# Main_board_V5_0.net
KiCad netlist of a schematic drawn in EAGLE
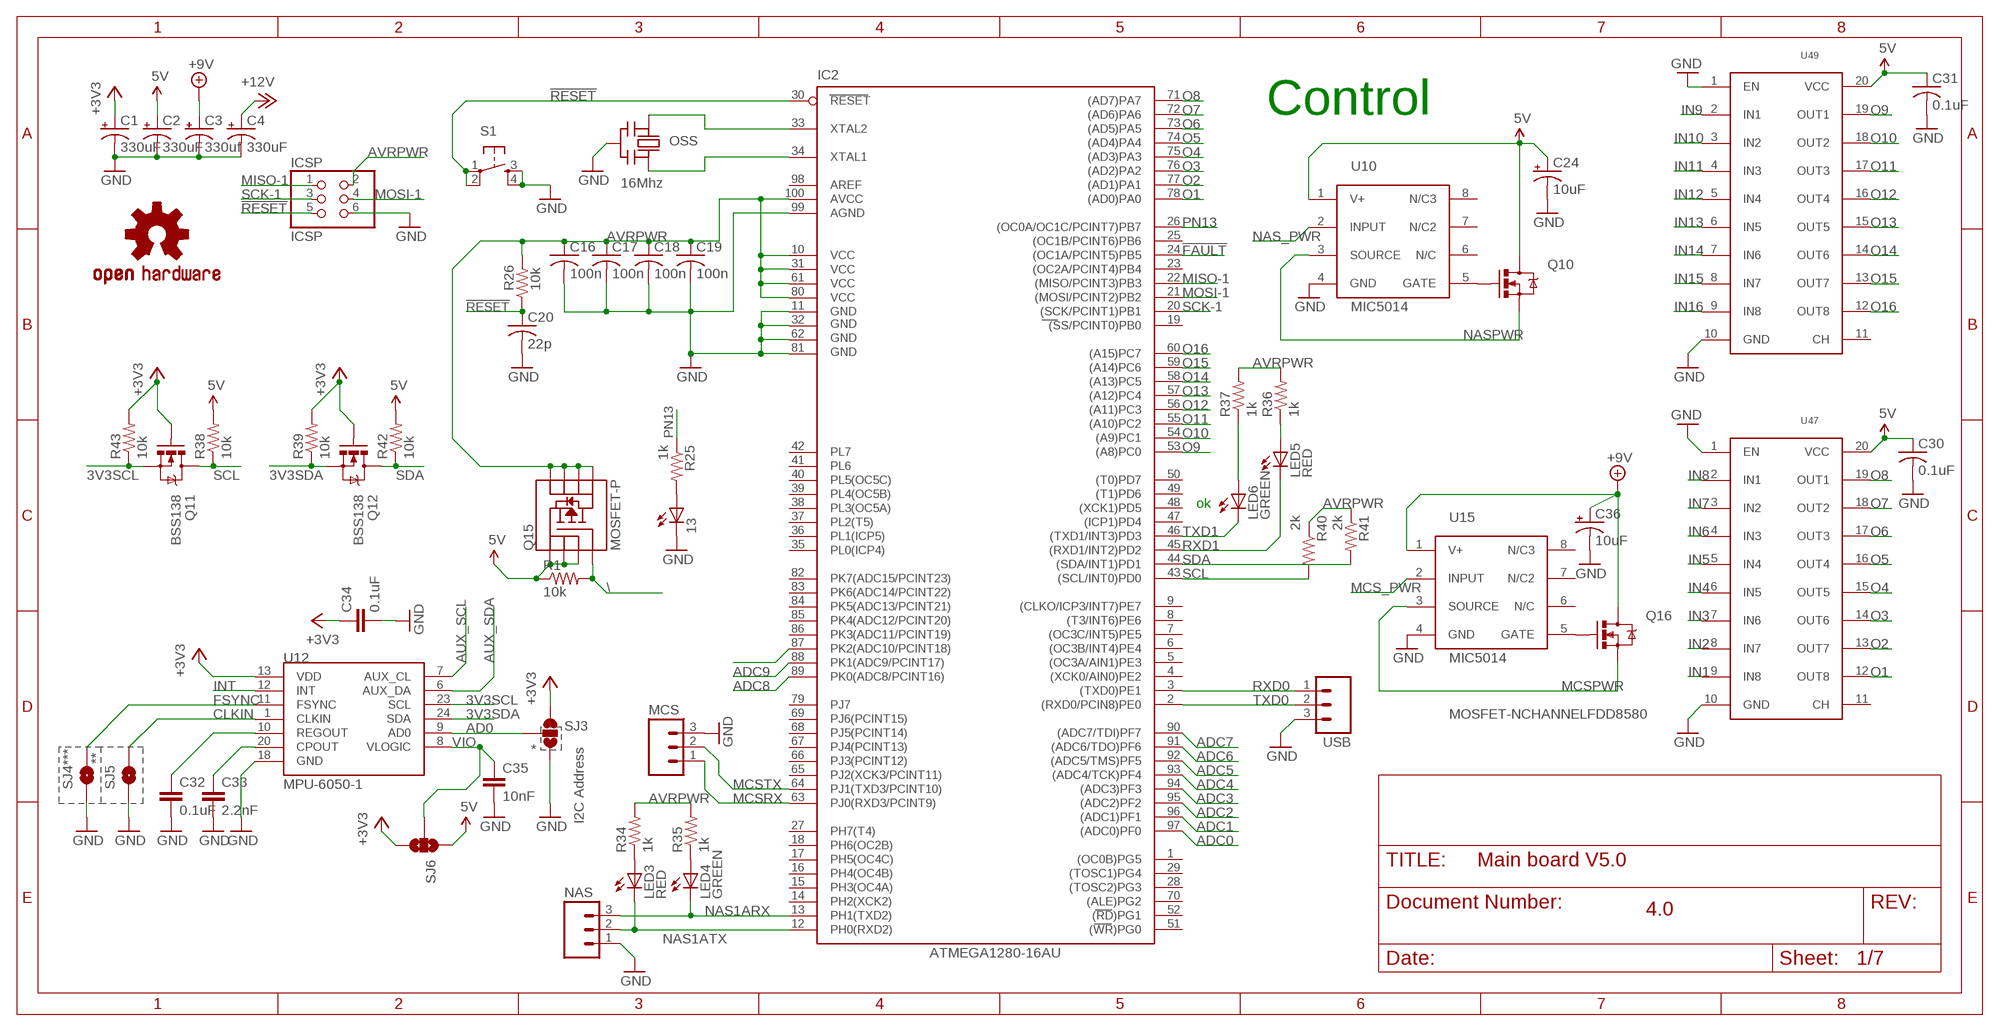
[diagram p0: schematic, sheet 1]
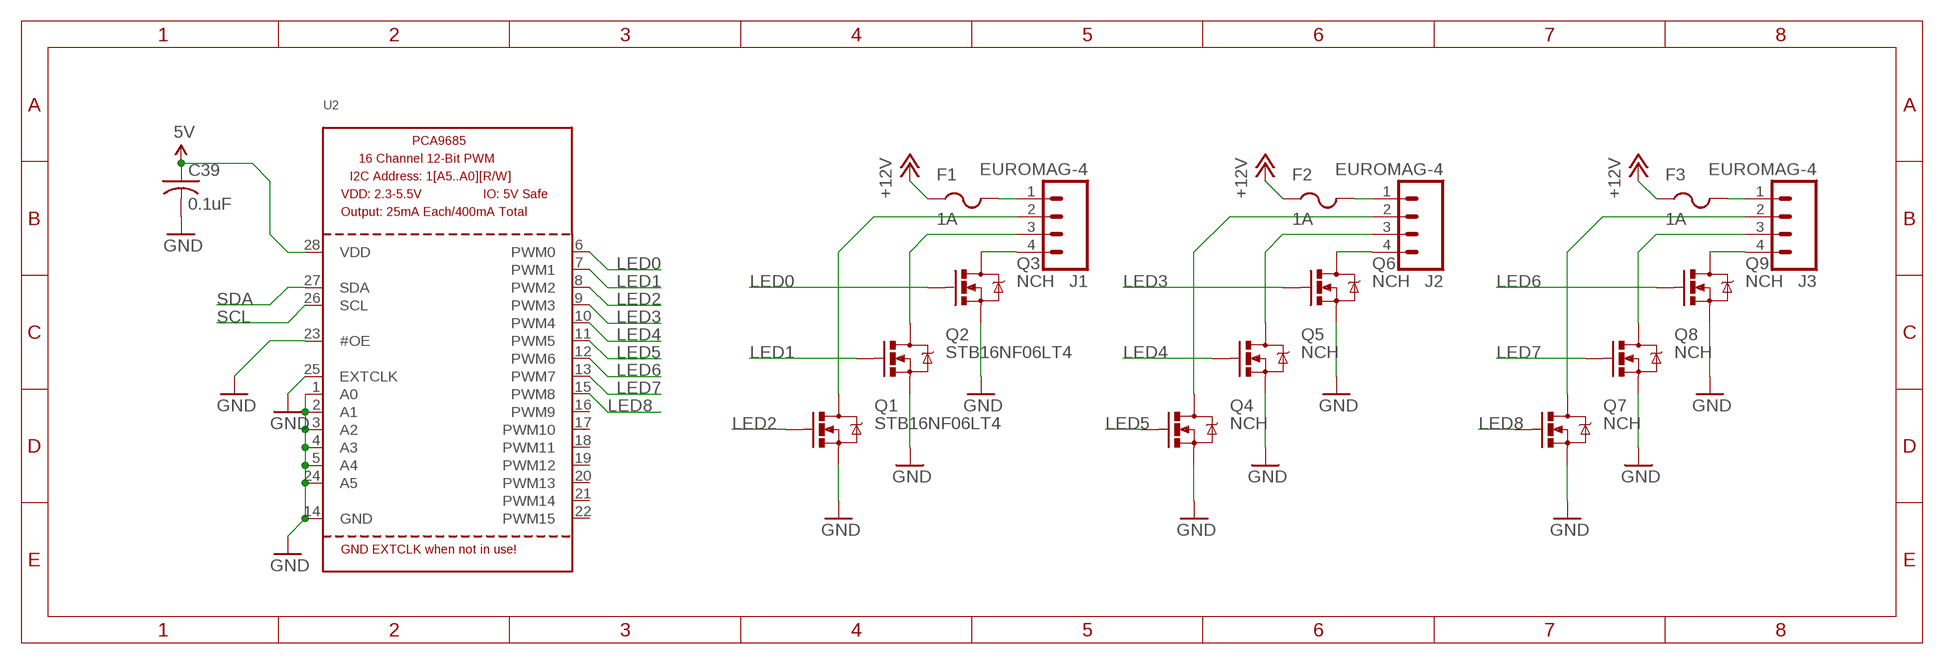
[diagram p1: schematic, sheet 2]
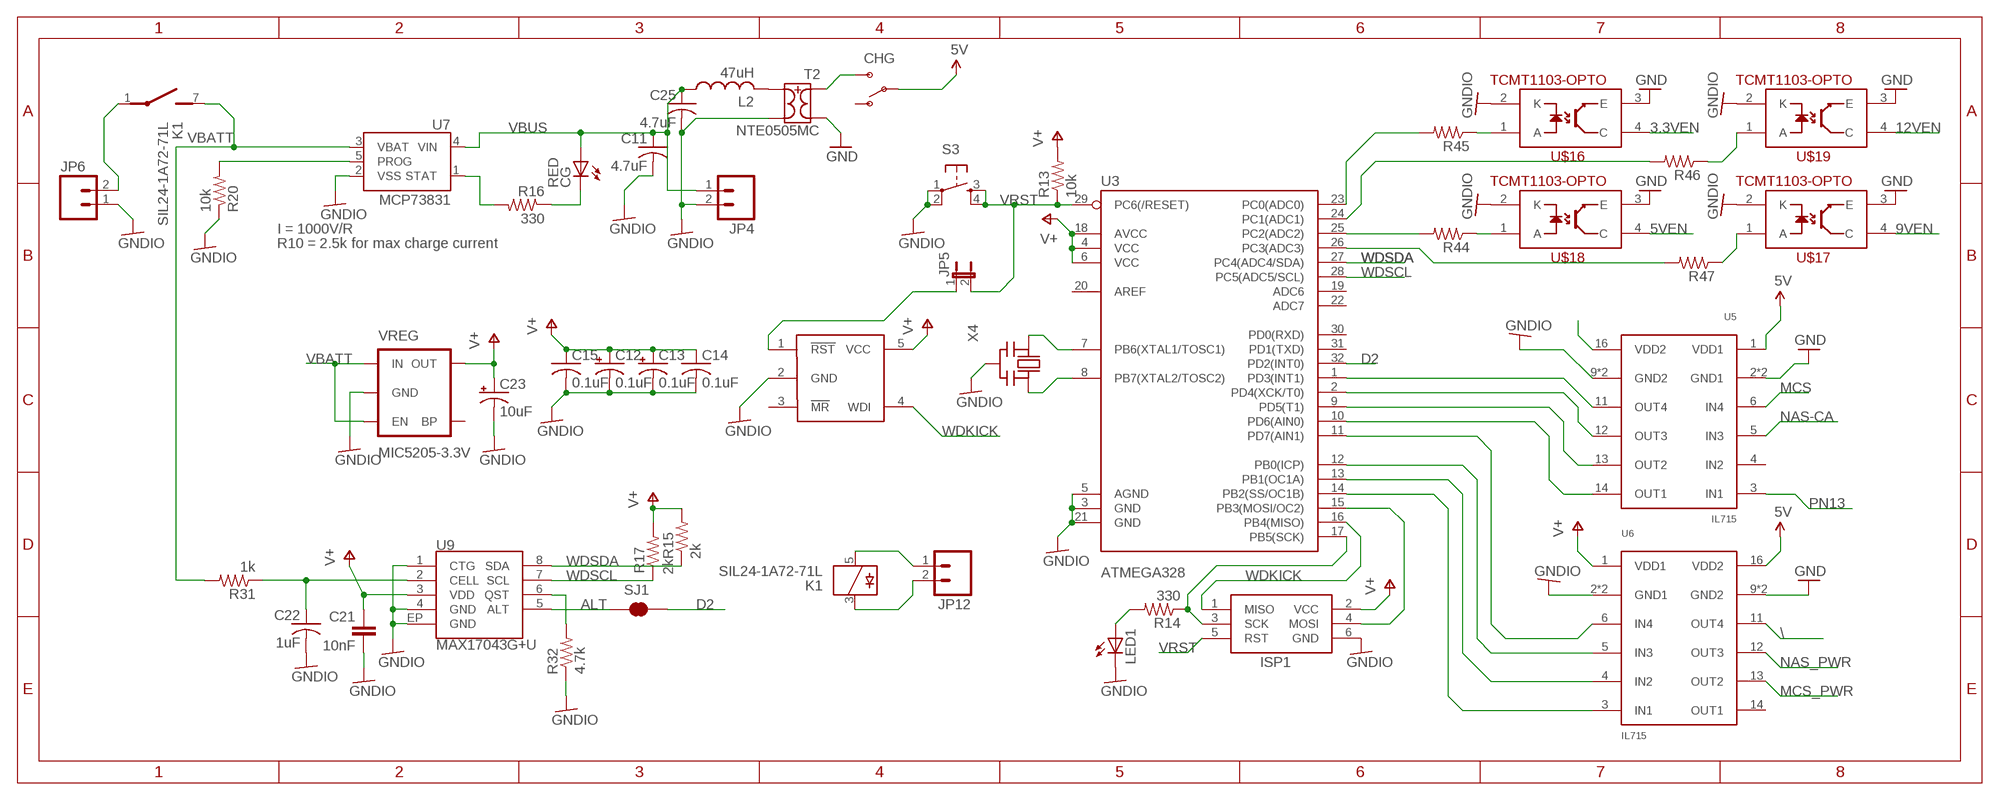
[diagram p2: schematic, sheet 3]
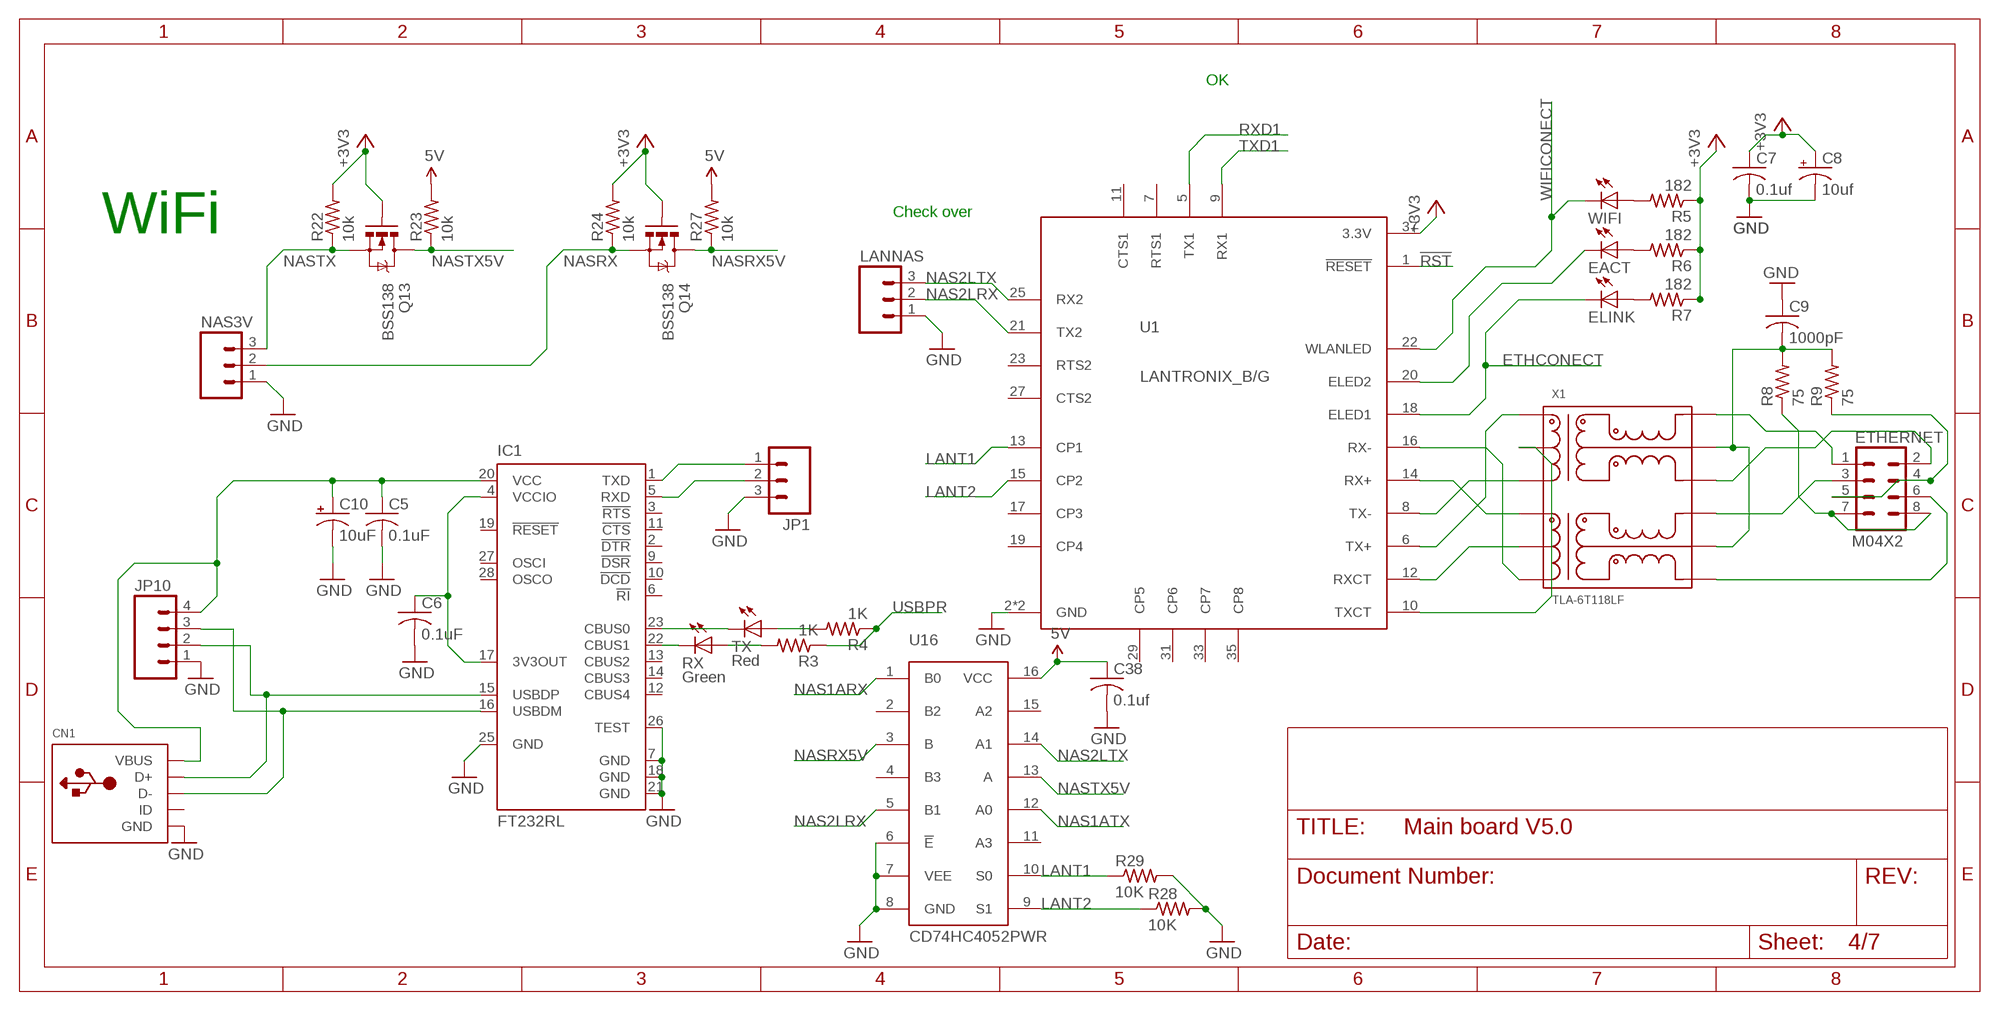
[diagram p3: schematic, sheet 4]
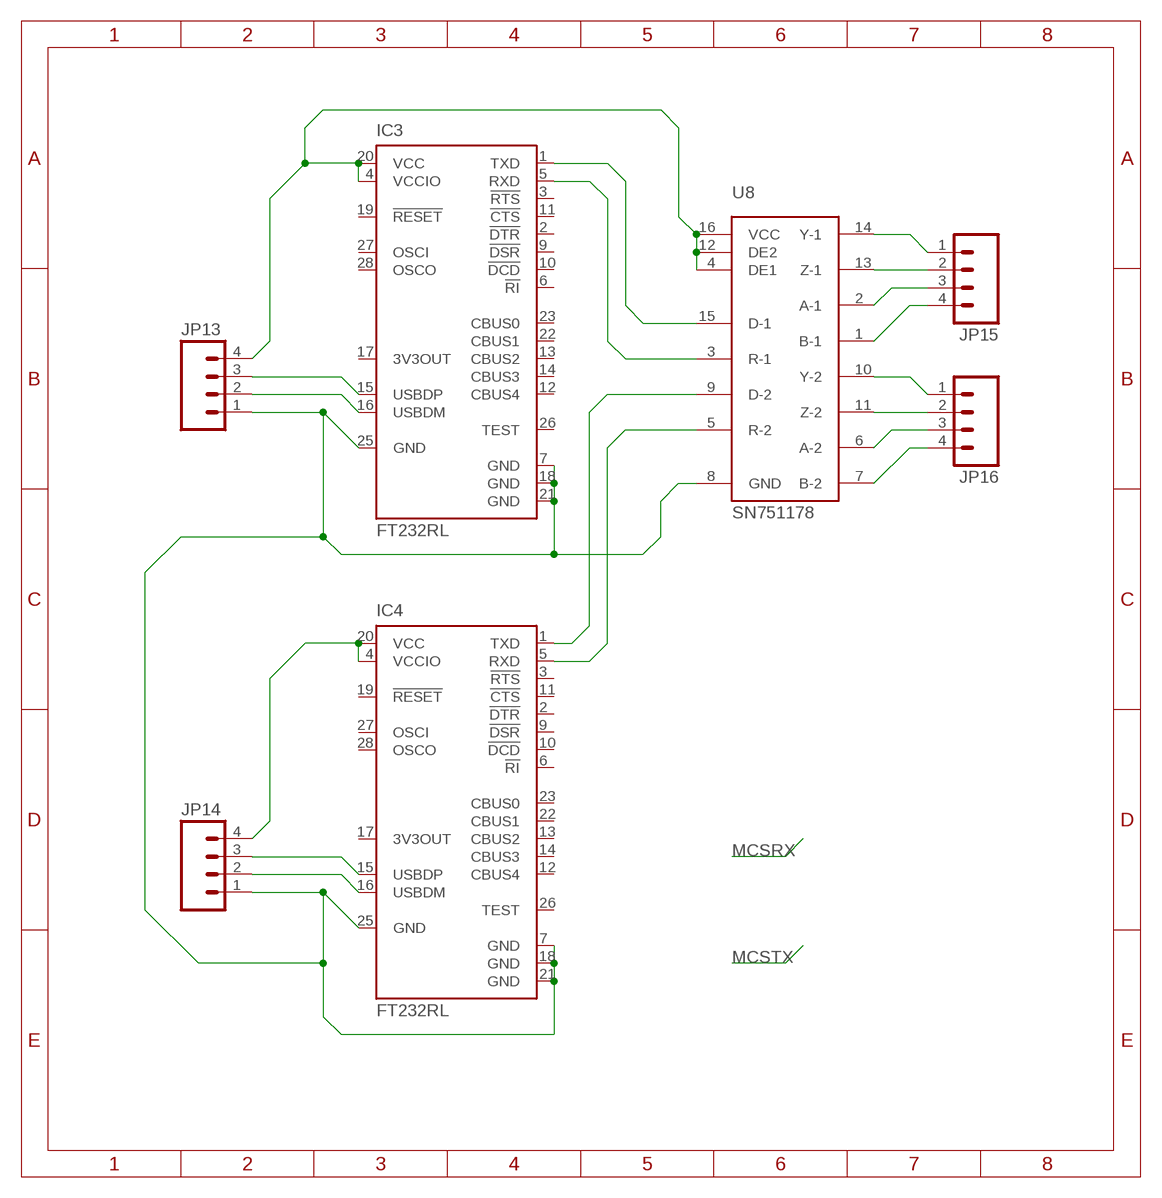
[diagram p4: schematic, sheet 5]
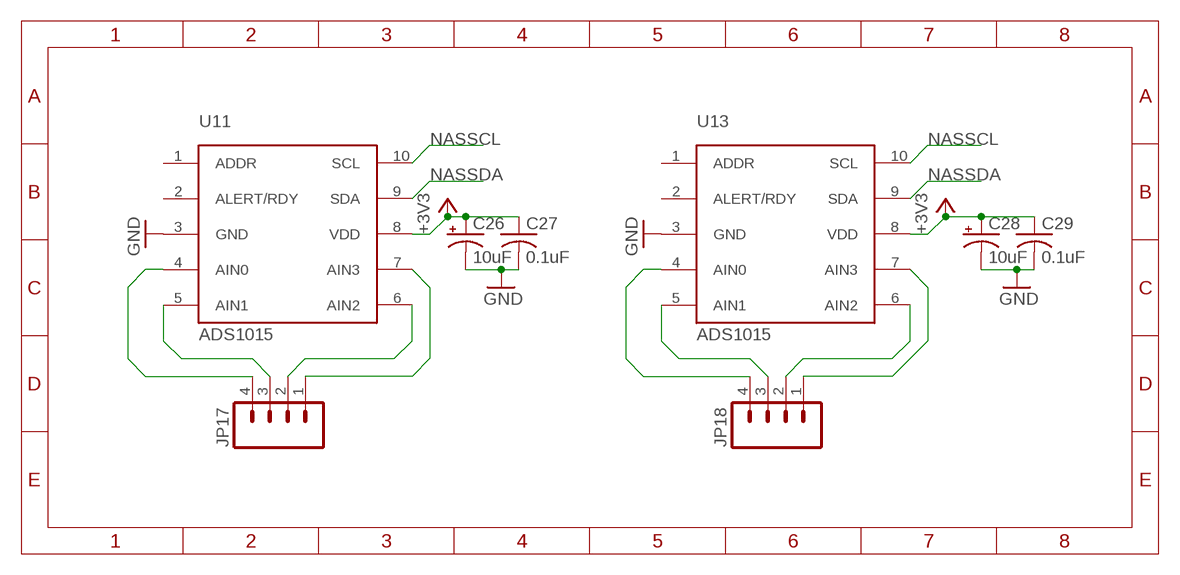
[diagram p5: schematic, sheet 6]
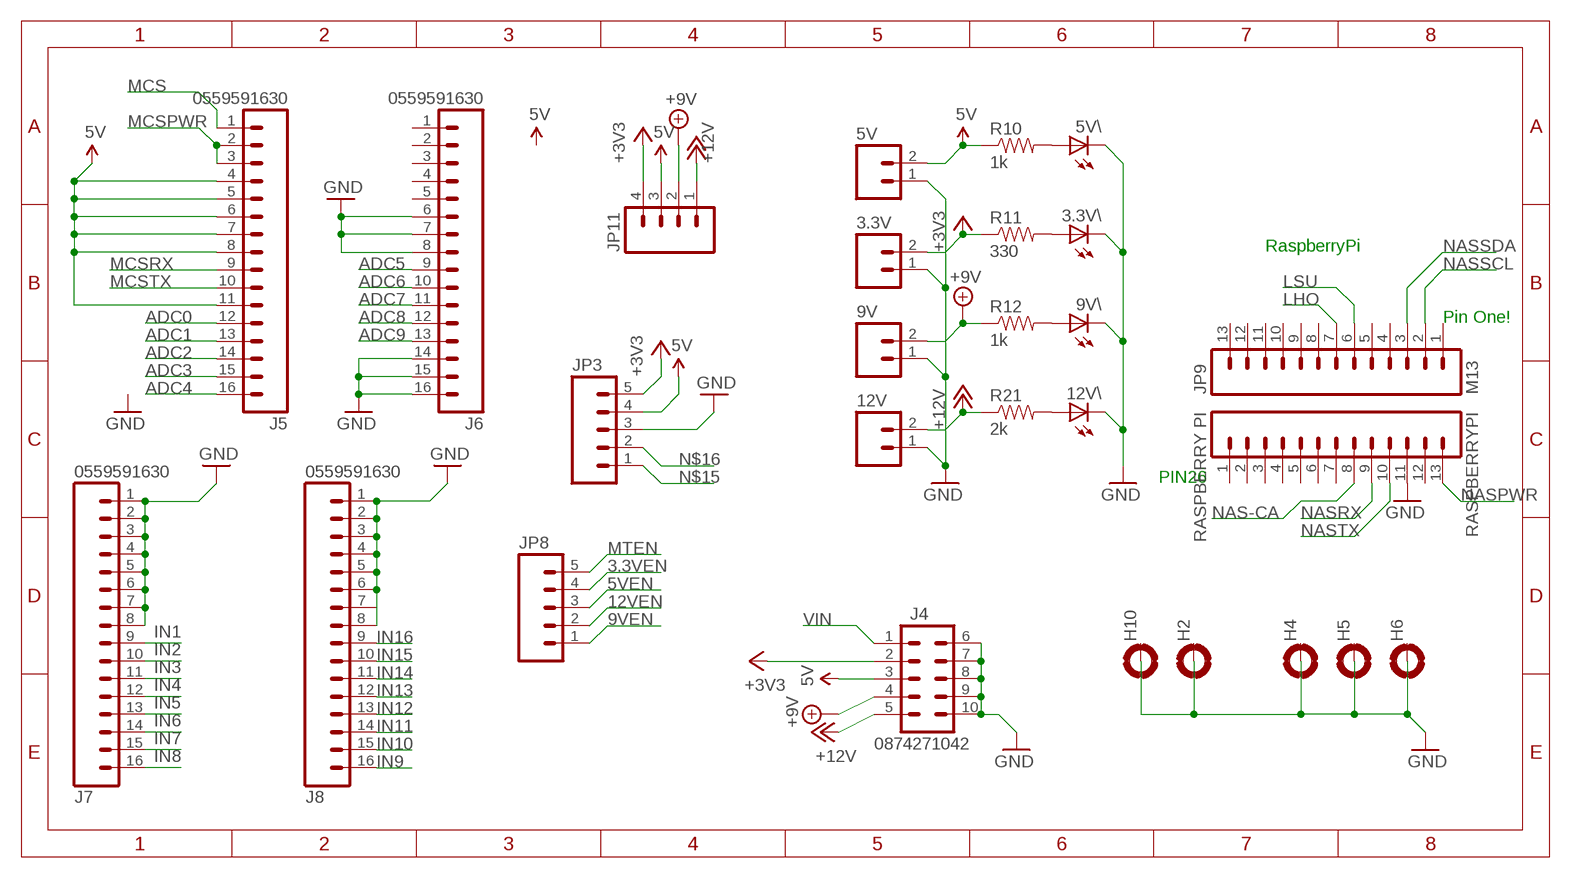
[diagram p6: schematic, sheet 7]

(export (version "E")
  (design (tool "Eeschema 10.0.6"))
  (components
    (comp (ref "C5")
      (value "0.1uF")
      (footprint "eagle-import:C0805K")
      (libsource (lib "eagle-import") (part "C-USC0805K"))
    )
    (comp (ref "C6")
      (value "0.1uF")
      (footprint "eagle-import:C0805K")
      (libsource (lib "eagle-import") (part "C-USC0805K"))
    )
    (comp (ref "C7")
      (value "0.1uf")
      (footprint "eagle-import:C0805K")
      (libsource (lib "eagle-import") (part "C-USC0805K"))
    )
    (comp (ref "C8")
      (value "10uf")
      (footprint "eagle-import:EIA3528")
      (libsource (lib "eagle-import") (part "CAP_POL3528"))
    )
    (comp (ref "C9")
      (value "1000pF")
      (footprint "eagle-import:C1812")
      (libsource (lib "eagle-import") (part "C-USC1812"))
    )
    (comp (ref "C10")
      (value "10uF")
      (footprint "eagle-import:EIA3528-KIT")
      (libsource (lib "eagle-import") (part "CAP_POL3528-KIT"))
    )
    (comp (ref "C38")
      (value "0.1uf")
      (footprint "eagle-import:C0805K")
      (libsource (lib "eagle-import") (part "C-USC0805K"))
    )
    (comp (ref "CN1")
      (value "USBMINIB")
      (footprint "eagle-import:USB-MINIB")
      (libsource (lib "eagle-import") (part "USBMINIB"))
    )
    (comp (ref "EACT")
      (value "LEDCHIP-LED0805")
      (footprint "eagle-import:CHIP-LED0805")
      (libsource (lib "eagle-import") (part "LEDCHIP-LED0805"))
    )
    (comp (ref "ELINK")
      (value "LEDCHIP-LED0805")
      (footprint "eagle-import:CHIP-LED0805")
      (libsource (lib "eagle-import") (part "LEDCHIP-LED0805"))
    )
    (comp (ref "ETHERNET")
      (value "M04X2")
      (footprint "eagle-import:2X4")
      (libsource (lib "eagle-import") (part "M04X2"))
    )
    (comp (ref "IC1")
      (value "FT232RL")
      (footprint "eagle-import:SSOP28")
      (libsource (lib "eagle-import") (part "FT232RL"))
    )
    (comp (ref "JP1")
      (value "M03POLAR")
      (footprint "eagle-import:MOLEX-1X3")
      (libsource (lib "eagle-import") (part "M03POLAR"))
    )
    (comp (ref "JP10")
      (value "M04POLAR")
      (footprint "eagle-import:MOLEX-1X4")
      (libsource (lib "eagle-import") (part "M04POLAR"))
    )
    (comp (ref "LANNAS")
      (value "M03POLAR")
      (footprint "eagle-import:MOLEX-1X3")
      (libsource (lib "eagle-import") (part "M03POLAR"))
    )
    (comp (ref "NAS3V")
      (value "M03LOCK_NO_SILK")
      (footprint "eagle-import:1X03_LOCK_NO_SILK")
      (libsource (lib "eagle-import") (part "M03LOCK_NO_SILK"))
    )
    (comp (ref "Q13")
      (value "BSS138")
      (footprint "eagle-import:SOT23-3")
      (libsource (lib "eagle-import") (part "MOSFET-NCHANNELSMD"))
    )
    (comp (ref "Q14")
      (value "BSS138")
      (footprint "eagle-import:SOT23-3")
      (libsource (lib "eagle-import") (part "MOSFET-NCHANNELSMD"))
    )
    (comp (ref "R3")
      (value "1K")
      (footprint "eagle-import:R0805")
      (libsource (lib "eagle-import") (part "R-US_R0805"))
    )
    (comp (ref "R4")
      (value "1K")
      (footprint "eagle-import:R0805")
      (libsource (lib "eagle-import") (part "R-US_R0805"))
    )
    (comp (ref "R5")
      (value "182")
      (footprint "eagle-import:R0805")
      (libsource (lib "eagle-import") (part "R-US_R0805"))
    )
    (comp (ref "R6")
      (value "182")
      (footprint "eagle-import:R0805")
      (libsource (lib "eagle-import") (part "R-US_R0805"))
    )
    (comp (ref "R7")
      (value "182")
      (footprint "eagle-import:R0805")
      (libsource (lib "eagle-import") (part "R-US_R0805"))
    )
    (comp (ref "R8")
      (value "75")
      (footprint "eagle-import:R0805")
      (libsource (lib "eagle-import") (part "R-US_R0805"))
    )
    (comp (ref "R9")
      (value "75")
      (footprint "eagle-import:R0805")
      (libsource (lib "eagle-import") (part "R-US_R0805"))
    )
    (comp (ref "R22")
      (value "10k")
      (footprint "eagle-import:R0805")
      (libsource (lib "eagle-import") (part "R-US_R0805"))
    )
    (comp (ref "R23")
      (value "10k")
      (footprint "eagle-import:R0805")
      (libsource (lib "eagle-import") (part "R-US_R0805"))
    )
    (comp (ref "R24")
      (value "10k")
      (footprint "eagle-import:R0805")
      (libsource (lib "eagle-import") (part "R-US_R0805"))
    )
    (comp (ref "R27")
      (value "10k")
      (footprint "eagle-import:R0805")
      (libsource (lib "eagle-import") (part "R-US_R0805"))
    )
    (comp (ref "R28")
      (value "10K")
      (footprint "eagle-import:R0805")
      (libsource (lib "eagle-import") (part "R-US_R0805"))
    )
    (comp (ref "R29")
      (value "10K")
      (footprint "eagle-import:R0805")
      (libsource (lib "eagle-import") (part "R-US_R0805"))
    )
    (comp (ref "RX")
      (value "Green")
      (footprint "eagle-import:CHIP-LED0805")
      (libsource (lib "eagle-import") (part "LEDCHIP-LED0805"))
    )
    (comp (ref "TX")
      (value "Red")
      (footprint "eagle-import:CHIP-LED0805")
      (libsource (lib "eagle-import") (part "LEDCHIP-LED0805"))
    )
    (comp (ref "U1")
      (value "LANTRONIX_B/G")
      (footprint "eagle-import:LANA_BTH")
      (libsource (lib "eagle-import") (part "LANTRONIX_A/B"))
    )
    (comp (ref "U16")
      (value "CD74HC4052PWR")
      (footprint "eagle-import:TSSOP-16")
      (libsource (lib "eagle-import") (part "CD74HC4052PWR"))
    )
    (comp (ref "WIFI")
      (value "LEDCHIP-LED0805")
      (footprint "eagle-import:CHIP-LED0805")
      (libsource (lib "eagle-import") (part "LEDCHIP-LED0805"))
    )
    (comp (ref "X1")
      (value "TLA-6T118LF")
      (footprint "eagle-import:SO-16MOD")
      (libsource (lib "eagle-import") (part "TLA-6T118LF"))
    )
    (comp (ref "C39")
      (value "0.1uF")
      (footprint "eagle-import:C0603")
      (libsource (lib "eagle-import") (part "minimidi_C-USC0603"))
    )
    (comp (ref "F1")
      (value "1A")
      (footprint "eagle-import:1812")
      (libsource (lib "eagle-import") (part "PTCFUSE-1812"))
    )
    (comp (ref "F2")
      (value "1A")
      (footprint "eagle-import:1812")
      (libsource (lib "eagle-import") (part "PTCFUSE-1812"))
    )
    (comp (ref "F3")
      (value "1A")
      (footprint "eagle-import:1812")
      (libsource (lib "eagle-import") (part "PTCFUSE-1812"))
    )
    (comp (ref "J1")
      (value "EUROMAG-4")
      (footprint "eagle-import:M4")
      (libsource (lib "eagle-import") (part "EUROMAG-4"))
    )
    (comp (ref "J2")
      (value "EUROMAG-4")
      (footprint "eagle-import:M4")
      (libsource (lib "eagle-import") (part "EUROMAG-4"))
    )
    (comp (ref "J3")
      (value "EUROMAG-4")
      (footprint "eagle-import:M4")
      (libsource (lib "eagle-import") (part "EUROMAG-4"))
    )
    (comp (ref "Q1")
      (value "STB16NF06LT4")
      (footprint "eagle-import:DPAK")
      (libsource (lib "eagle-import") (part "MOSFET-NCHANNELFDD8580"))
    )
    (comp (ref "Q2")
      (value "STB16NF06LT4")
      (footprint "eagle-import:DPAK")
      (libsource (lib "eagle-import") (part "MOSFET-NCHANNELFDD8580"))
    )
    (comp (ref "Q3")
      (value "NCH")
      (footprint "eagle-import:DPAK")
      (libsource (lib "eagle-import") (part "MOSFET-NCHANNELFDD8580"))
    )
    (comp (ref "Q4")
      (value "NCH")
      (footprint "eagle-import:DPAK")
      (libsource (lib "eagle-import") (part "MOSFET-NCHANNELFDD8580"))
    )
    (comp (ref "Q5")
      (value "NCH")
      (footprint "eagle-import:DPAK")
      (libsource (lib "eagle-import") (part "MOSFET-NCHANNELFDD8580"))
    )
    (comp (ref "Q6")
      (value "NCH")
      (footprint "eagle-import:DPAK")
      (libsource (lib "eagle-import") (part "MOSFET-NCHANNELFDD8580"))
    )
    (comp (ref "Q7")
      (value "NCH")
      (footprint "eagle-import:DPAK")
      (libsource (lib "eagle-import") (part "MOSFET-NCHANNELFDD8580"))
    )
    (comp (ref "Q8")
      (value "NCH")
      (footprint "eagle-import:DPAK")
      (libsource (lib "eagle-import") (part "MOSFET-NCHANNELFDD8580"))
    )
    (comp (ref "Q9")
      (value "NCH")
      (footprint "eagle-import:DPAK")
      (libsource (lib "eagle-import") (part "MOSFET-NCHANNELFDD8580"))
    )
    (comp (ref "U2")
      (value "PCA9685")
      (footprint "eagle-import:TSSOP28")
      (libsource (lib "eagle-import") (part "PCA9685"))
    )
    (comp (ref "13")
      (value "LEDCHIP-LED0805")
      (footprint "eagle-import:CHIP-LED0805")
      (libsource (lib "eagle-import") (part "LEDCHIP-LED0805"))
    )
    (comp (ref "C1")
      (value "330uF")
      (footprint "eagle-import:140CLH-0810")
      (libsource (lib "eagle-import") (part "CPOL-US140CLH-0810"))
    )
    (comp (ref "C2")
      (value "330uF")
      (footprint "eagle-import:140CLH-0810")
      (libsource (lib "eagle-import") (part "CPOL-US140CLH-0810"))
    )
    (comp (ref "C3")
      (value "330uf")
      (footprint "eagle-import:140CLH-0810")
      (libsource (lib "eagle-import") (part "CPOL-US140CLH-0810"))
    )
    (comp (ref "C4")
      (value "330uF")
      (footprint "eagle-import:140CLH-0810")
      (libsource (lib "eagle-import") (part "CPOL-US140CLH-0810"))
    )
    (comp (ref "C16")
      (value "100n")
      (footprint "eagle-import:C0805")
      (libsource (lib "eagle-import") (part "C-USC0805"))
    )
    (comp (ref "C17")
      (value "100n")
      (footprint "eagle-import:C0805")
      (libsource (lib "eagle-import") (part "C-USC0805"))
    )
    (comp (ref "C18")
      (value "100n")
      (footprint "eagle-import:C0805")
      (libsource (lib "eagle-import") (part "C-USC0805"))
    )
    (comp (ref "C19")
      (value "100n")
      (footprint "eagle-import:C0805")
      (libsource (lib "eagle-import") (part "C-USC0805"))
    )
    (comp (ref "C20")
      (value "22p")
      (footprint "eagle-import:C0805")
      (libsource (lib "eagle-import") (part "C-USC0805"))
    )
    (comp (ref "C24")
      (value "10uF")
      (footprint "eagle-import:CT6032")
      (libsource (lib "eagle-import") (part "CPOL-USCT6032"))
    )
    (comp (ref "C30")
      (value "0.1uF")
      (footprint "eagle-import:C0805")
      (libsource (lib "eagle-import") (part "C-USC0805"))
    )
    (comp (ref "C31")
      (value "0.1uF")
      (footprint "eagle-import:C0805")
      (libsource (lib "eagle-import") (part "C-USC0805"))
    )
    (comp (ref "C32")
      (value "0.1uF")
      (footprint "eagle-import:0805")
      (libsource (lib "eagle-import") (part "CAP0805"))
    )
    (comp (ref "C33")
      (value "2.2nF")
      (footprint "eagle-import:0805")
      (libsource (lib "eagle-import") (part "CAP0805"))
    )
    (comp (ref "C34")
      (value "0.1uF")
      (footprint "eagle-import:0805")
      (libsource (lib "eagle-import") (part "CAP0805"))
    )
    (comp (ref "C35")
      (value "10nF")
      (footprint "eagle-import:0805")
      (libsource (lib "eagle-import") (part "CAP0805"))
    )
    (comp (ref "C36")
      (value "10uF")
      (footprint "eagle-import:CT6032")
      (libsource (lib "eagle-import") (part "CPOL-USCT6032"))
    )
    (comp (ref "IC2")
      (value "ATMEGA1280-16AU")
      (footprint "eagle-import:TQFP100")
      (libsource (lib "eagle-import") (part "ATMEGAAU1280-16"))
    )
    (comp (ref "ICSP")
      (value "ICSP")
      (footprint "eagle-import:2X03")
      (libsource (lib "eagle-import") (part "PINHD-2X3"))
    )
    (comp (ref "LED3")
      (value "RED")
      (footprint "eagle-import:CHIP-LED0805")
      (libsource (lib "eagle-import") (part "LEDCHIP-LED0805"))
    )
    (comp (ref "LED4")
      (value "GREEN")
      (footprint "eagle-import:CHIP-LED0805")
      (libsource (lib "eagle-import") (part "LEDCHIP-LED0805"))
    )
    (comp (ref "LED5")
      (value "RED")
      (footprint "eagle-import:CHIP-LED0805")
      (libsource (lib "eagle-import") (part "LEDCHIP-LED0805"))
    )
    (comp (ref "LED6")
      (value "GREEN")
      (footprint "eagle-import:CHIP-LED0805")
      (libsource (lib "eagle-import") (part "LEDCHIP-LED0805"))
    )
    (comp (ref "MCS")
      (value "M03LOCK")
      (footprint "eagle-import:1X03_LOCK")
      (libsource (lib "eagle-import") (part "M03LOCK"))
    )
    (comp (ref "NAS")
      (value "M03POLAR")
      (footprint "eagle-import:MOLEX-1X3")
      (libsource (lib "eagle-import") (part "M03POLAR"))
    )
    (comp (ref "OSS")
      (value "16Mhz")
      (footprint "eagle-import:AWCSR")
      (libsource (lib "eagle-import") (part "CERMOSCILL-AWCSR"))
    )
    (comp (ref "Q10")
      (value "MOSFET-NCHANNELFDD8580")
      (footprint "eagle-import:DPAK")
      (libsource (lib "eagle-import") (part "MOSFET-NCHANNELFDD8580"))
    )
    (comp (ref "Q11")
      (value "BSS138")
      (footprint "eagle-import:SOT23-3")
      (libsource (lib "eagle-import") (part "MOSFET-NCHANNELSMD"))
    )
    (comp (ref "Q12")
      (value "BSS138")
      (footprint "eagle-import:SOT23-3")
      (libsource (lib "eagle-import") (part "MOSFET-NCHANNELSMD"))
    )
    (comp (ref "Q15")
      (value "MOSFET-P")
      (footprint "eagle-import:SO08")
      (libsource (lib "eagle-import") (part "MOSFET-PCHANNEL-SOIC8SOIC8"))
    )
    (comp (ref "Q16")
      (value "MOSFET-NCHANNELFDD8580")
      (footprint "eagle-import:DPAK")
      (libsource (lib "eagle-import") (part "MOSFET-NCHANNELFDD8580"))
    )
    (comp (ref "R1")
      (value "10k")
      (footprint "eagle-import:R0805")
      (libsource (lib "eagle-import") (part "R-US_R0805"))
    )
    (comp (ref "R25")
      (value "1k")
      (footprint "eagle-import:R0805")
      (libsource (lib "eagle-import") (part "R-US_R0805"))
    )
    (comp (ref "R26")
      (value "10k")
      (footprint "eagle-import:R0805")
      (libsource (lib "eagle-import") (part "R-US_R0805"))
    )
    (comp (ref "R34")
      (value "1k")
      (footprint "eagle-import:R0805")
      (libsource (lib "eagle-import") (part "R-US_R0805"))
    )
    (comp (ref "R35")
      (value "1k")
      (footprint "eagle-import:R0805")
      (libsource (lib "eagle-import") (part "R-US_R0805"))
    )
    (comp (ref "R36")
      (value "1k")
      (footprint "eagle-import:R0805")
      (libsource (lib "eagle-import") (part "R-US_R0805"))
    )
    (comp (ref "R37")
      (value "1k")
      (footprint "eagle-import:R0805")
      (libsource (lib "eagle-import") (part "R-US_R0805"))
    )
    (comp (ref "R38")
      (value "10k")
      (footprint "eagle-import:R0805")
      (libsource (lib "eagle-import") (part "R-US_R0805"))
    )
    (comp (ref "R39")
      (value "10k")
      (footprint "eagle-import:R0805")
      (libsource (lib "eagle-import") (part "R-US_R0805"))
    )
    (comp (ref "R40")
      (value "2k")
      (footprint "eagle-import:R0805")
      (libsource (lib "eagle-import") (part "R-US_R0805"))
    )
    (comp (ref "R41")
      (value "2k")
      (footprint "eagle-import:R0805")
      (libsource (lib "eagle-import") (part "R-US_R0805"))
    )
    (comp (ref "R42")
      (value "10k")
      (footprint "eagle-import:R0805")
      (libsource (lib "eagle-import") (part "R-US_R0805"))
    )
    (comp (ref "R43")
      (value "10k")
      (footprint "eagle-import:R0805")
      (libsource (lib "eagle-import") (part "R-US_R0805"))
    )
    (comp (ref "S1")
      (value "TAC_SWITCHSMD")
      (footprint "eagle-import:TACTILE_SWITCH_SMD")
      (libsource (lib "eagle-import") (part "TAC_SWITCHSMD"))
    )
    (comp (ref "SJ3")
      (value "SOLDERJUMPER_2WAYPASTE2&3")
      (footprint "eagle-import:SJ_3_PASTE2&3")
      (libsource (lib "eagle-import") (part "SOLDERJUMPER_2WAYPASTE2&3"))
    )
    (comp (ref "SJ4")
      (value "SOLDERJUMPERTRACE")
      (footprint "eagle-import:SJ_2S-TRACE")
      (libsource (lib "eagle-import") (part "SOLDERJUMPERTRACE"))
    )
    (comp (ref "SJ5")
      (value "SOLDERJUMPERTRACE")
      (footprint "eagle-import:SJ_2S-TRACE")
      (libsource (lib "eagle-import") (part "SOLDERJUMPERTRACE"))
    )
    (comp (ref "SJ6")
      (value "SOLDERJUMPER_2WAYPASTE2&3")
      (footprint "eagle-import:SJ_3_PASTE2&3")
      (libsource (lib "eagle-import") (part "SOLDERJUMPER_2WAYPASTE2&3"))
    )
    (comp (ref "U$3")
      (value "OSHW-LOGOL")
      (footprint "eagle-import:OSHW-LOGO-L")
      (libsource (lib "eagle-import") (part "OSHW-LOGOL"))
    )
    (comp (ref "U10")
      (value "MIC5014")
      (footprint "eagle-import:SO08")
      (libsource (lib "eagle-import") (part "MIC5014"))
    )
    (comp (ref "U12")
      (value "MPU-6050-1")
      (footprint "eagle-import:QFN-24-4MM2")
      (libsource (lib "eagle-import") (part "MPU-6050-1"))
    )
    (comp (ref "U15")
      (value "MIC5014")
      (footprint "eagle-import:SO08")
      (libsource (lib "eagle-import") (part "MIC5014"))
    )
    (comp (ref "U47")
      (value "MAX6818")
      (footprint "eagle-import:SSOP-20")
      (libsource (lib "eagle-import") (part "MAX6818"))
    )
    (comp (ref "U49")
      (value "MAX6818")
      (footprint "eagle-import:SSOP-20")
      (libsource (lib "eagle-import") (part "MAX6818"))
    )
    (comp (ref "USB")
      (value "M03LOCK")
      (footprint "eagle-import:1X03_LOCK")
      (libsource (lib "eagle-import") (part "M03LOCK"))
    )
    (comp (ref "3.3V")
      (value "EUROMAG-290DEG")
      (footprint "eagle-import:M2")
      (libsource (lib "eagle-import") (part "EUROMAG-290DEG"))
    )
    (comp (ref "3.3V\\")
      (value "LED-FKIT-1206")
      (footprint "eagle-import:FKIT-LED-1206")
      (libsource (lib "eagle-import") (part "LED-FKIT-1206"))
    )
    (comp (ref "5V")
      (value "EUROMAG-290DEG")
      (footprint "eagle-import:M2")
      (libsource (lib "eagle-import") (part "EUROMAG-290DEG"))
    )
    (comp (ref "5V\\")
      (value "LED-FKIT-1206")
      (footprint "eagle-import:FKIT-LED-1206")
      (libsource (lib "eagle-import") (part "LED-FKIT-1206"))
    )
    (comp (ref "9V")
      (value "EUROMAG-290DEG")
      (footprint "eagle-import:M2")
      (libsource (lib "eagle-import") (part "EUROMAG-290DEG"))
    )
    (comp (ref "9V\\")
      (value "LED-FKIT-1206")
      (footprint "eagle-import:FKIT-LED-1206")
      (libsource (lib "eagle-import") (part "LED-FKIT-1206"))
    )
    (comp (ref "12V")
      (value "EUROMAG-290DEG")
      (footprint "eagle-import:M2")
      (libsource (lib "eagle-import") (part "EUROMAG-290DEG"))
    )
    (comp (ref "12V\\")
      (value "LED-FKIT-1206")
      (footprint "eagle-import:FKIT-LED-1206")
      (libsource (lib "eagle-import") (part "LED-FKIT-1206"))
    )
    (comp (ref "H2")
      (value "MOUNT-PAD-ROUND2.8")
      (footprint "eagle-import:2,8-PAD")
      (libsource (lib "eagle-import") (part "MOUNT-PAD-ROUND2.8"))
    )
    (comp (ref "H4")
      (value "MOUNT-PAD-ROUND2.8")
      (footprint "eagle-import:2,8-PAD")
      (libsource (lib "eagle-import") (part "MOUNT-PAD-ROUND2.8"))
    )
    (comp (ref "H5")
      (value "MOUNT-PAD-ROUND2.8")
      (footprint "eagle-import:2,8-PAD")
      (libsource (lib "eagle-import") (part "MOUNT-PAD-ROUND2.8"))
    )
    (comp (ref "H6")
      (value "MOUNT-PAD-ROUND2.8")
      (footprint "eagle-import:2,8-PAD")
      (libsource (lib "eagle-import") (part "MOUNT-PAD-ROUND2.8"))
    )
    (comp (ref "H10")
      (value "MOUNT-PAD-ROUND2.8")
      (footprint "eagle-import:2,8-PAD")
      (libsource (lib "eagle-import") (part "MOUNT-PAD-ROUND2.8"))
    )
    (comp (ref "J4")
      (value "0874271042")
      (footprint "eagle-import:0874271042")
      (libsource (lib "eagle-import") (part "0874271042"))
    )
    (comp (ref "J5")
      (value "0559591630")
      (footprint "eagle-import:0559591630")
      (libsource (lib "eagle-import") (part "0559591630"))
    )
    (comp (ref "J6")
      (value "0559591630")
      (footprint "eagle-import:0559591630")
      (libsource (lib "eagle-import") (part "0559591630"))
    )
    (comp (ref "J7")
      (value "0559591630")
      (footprint "eagle-import:0559591630")
      (libsource (lib "eagle-import") (part "0559591630"))
    )
    (comp (ref "J8")
      (value "0559591630")
      (footprint "eagle-import:0559591630")
      (libsource (lib "eagle-import") (part "0559591630"))
    )
    (comp (ref "JP3")
      (value "M05LOCK_LONGPADS")
      (footprint "eagle-import:1X05_LOCK_LONGPADS")
      (libsource (lib "eagle-import") (part "M05LOCK_LONGPADS"))
    )
    (comp (ref "JP8")
      (value "M05LOCK_LONGPADS")
      (footprint "eagle-import:1X05_LOCK_LONGPADS")
      (libsource (lib "eagle-import") (part "M05LOCK_LONGPADS"))
    )
    (comp (ref "JP9")
      (value "M13")
      (footprint "eagle-import:1X13")
      (libsource (lib "eagle-import") (part "M13"))
    )
    (comp (ref "JP11")
      (value "M04POLAR")
      (footprint "eagle-import:MOLEX-1X4")
      (libsource (lib "eagle-import") (part "M04POLAR"))
    )
    (comp (ref "R10")
      (value "1k")
      (footprint "eagle-import:0805")
      (libsource (lib "eagle-import") (part "RESISTOR0805-RES"))
    )
    (comp (ref "R11")
      (value "330")
      (footprint "eagle-import:0805")
      (libsource (lib "eagle-import") (part "RESISTOR0805-RES"))
    )
    (comp (ref "R12")
      (value "1k")
      (footprint "eagle-import:0805")
      (libsource (lib "eagle-import") (part "RESISTOR0805-RES"))
    )
    (comp (ref "R21")
      (value "2k")
      (footprint "eagle-import:0805")
      (libsource (lib "eagle-import") (part "RESISTOR0805-RES"))
    )
    (comp (ref "RASPBERRYPI")
      (value "RASPBERRY PI")
      (footprint "eagle-import:1X13")
      (libsource (lib "eagle-import") (part "M13"))
    )
    (comp (ref "IC3")
      (value "FT232RL")
      (footprint "eagle-import:SSOP28")
      (libsource (lib "eagle-import") (part "FT232RL"))
    )
    (comp (ref "IC4")
      (value "FT232RL")
      (footprint "eagle-import:SSOP28")
      (libsource (lib "eagle-import") (part "FT232RL"))
    )
    (comp (ref "JP13")
      (value "M04SMD")
      (footprint "eagle-import:1X04-SMD")
      (libsource (lib "eagle-import") (part "M04SMD"))
    )
    (comp (ref "JP14")
      (value "M04SMD")
      (footprint "eagle-import:1X04-SMD")
      (libsource (lib "eagle-import") (part "M04SMD"))
    )
    (comp (ref "JP15")
      (value "M04SMD")
      (footprint "eagle-import:1X04-SMD")
      (libsource (lib "eagle-import") (part "M04SMD"))
    )
    (comp (ref "JP16")
      (value "M04SMD")
      (footprint "eagle-import:1X04-SMD")
      (libsource (lib "eagle-import") (part "M04SMD"))
    )
    (comp (ref "U8")
      (value "SN751178")
      (footprint "eagle-import:S016")
      (libsource (lib "eagle-import") (part "SN751178"))
    )
    (comp (ref "C11")
      (value "4.7uF")
      (footprint "eagle-import:C0603")
      (libsource (lib "eagle-import") (part "resistor_C-USC0603"))
    )
    (comp (ref "C12")
      (value "0.1uF")
      (footprint "eagle-import:CT3528")
      (libsource (lib "eagle-import") (part "CPOL-USCT3528"))
    )
    (comp (ref "C13")
      (value "0.1uF")
      (footprint "eagle-import:CT3528")
      (libsource (lib "eagle-import") (part "CPOL-USCT3528"))
    )
    (comp (ref "C14")
      (value "0.1uF")
      (footprint "eagle-import:C0805")
      (libsource (lib "eagle-import") (part "C-USC0805"))
    )
    (comp (ref "C15")
      (value "0.1uF")
      (footprint "eagle-import:C0805")
      (libsource (lib "eagle-import") (part "C-USC0805"))
    )
    (comp (ref "C21")
      (value "10nF")
      (footprint "eagle-import:0603-CAP")
      (libsource (lib "eagle-import") (part "CAP0603-CAP"))
    )
    (comp (ref "C22")
      (value "1uF")
      (footprint "eagle-import:C0603")
      (libsource (lib "eagle-import") (part "resistor_C-USC0603"))
    )
    (comp (ref "C23")
      (value "10uF")
      (footprint "eagle-import:CT3528")
      (libsource (lib "eagle-import") (part "CPOL-USCT3528"))
    )
    (comp (ref "C25")
      (value "4.7uF")
      (footprint "eagle-import:C0603")
      (libsource (lib "eagle-import") (part "resistor_C-USC0603"))
    )
    (comp (ref "CG")
      (value "RED")
      (footprint "eagle-import:SML0805")
      (libsource (lib "eagle-import") (part "LEDSML0805"))
    )
    (comp (ref "CHG")
      (value "SWITCH-SPSTPTH")
      (footprint "eagle-import:SWITCH-SPDT")
      (libsource (lib "eagle-import") (part "SWITCH-SPSTPTH"))
    )
    (comp (ref "ISP1")
      (value "AVRISP-6")
      (footprint "eagle-import:AVRISP")
      (libsource (lib "eagle-import") (part "AVRISP-6"))
    )
    (comp (ref "JP4")
      (value "M021X02_NO_SILK")
      (footprint "eagle-import:1X02_NO_SILK")
      (libsource (lib "eagle-import") (part "M021X02_NO_SILK"))
    )
    (comp (ref "JP5")
      (value "JUMPER-2PTH_LOCK")
      (footprint "eagle-import:1X02_LOCK")
      (libsource (lib "eagle-import") (part "JUMPER-2PTH_LOCK"))
    )
    (comp (ref "JP6")
      (value "M02-JST-2MM-SMT")
      (footprint "eagle-import:JST-2-SMD")
      (libsource (lib "eagle-import") (part "M02-JST-2MM-SMT"))
    )
    (comp (ref "JP12")
      (value "M02POLAR_LOCK")
      (footprint "eagle-import:MOLEX-1X2_LOCK")
      (libsource (lib "eagle-import") (part "M02POLAR_LOCK"))
    )
    (comp (ref "K1")
      (value "SIL24-1A72-71L")
      (footprint "eagle-import:REED")
      (libsource (lib "eagle-import") (part "35701331"))
    )
    (comp (ref "L2")
      (value "47uH")
      (footprint "eagle-import:L2012C")
      (libsource (lib "eagle-import") (part "L-USL2012C"))
    )
    (comp (ref "LED1")
      (value "LEDCHIPLED_0805")
      (footprint "eagle-import:CHIPLED_0805")
      (libsource (lib "eagle-import") (part "LEDCHIPLED_0805"))
    )
    (comp (ref "R13")
      (value "10k")
      (footprint "eagle-import:R0805")
      (libsource (lib "eagle-import") (part "resistor_R-US_R0805"))
    )
    (comp (ref "R14")
      (value "330")
      (footprint "eagle-import:R0805")
      (libsource (lib "eagle-import") (part "resistor_R-US_R0805"))
    )
    (comp (ref "R15")
      (value "2k")
      (footprint "eagle-import:R0805")
      (libsource (lib "eagle-import") (part "R-US_R0805"))
    )
    (comp (ref "R16")
      (value "330")
      (footprint "eagle-import:R0805")
      (libsource (lib "eagle-import") (part "resistor_R-US_R0805"))
    )
    (comp (ref "R17")
      (value "2k")
      (footprint "eagle-import:R0805")
      (libsource (lib "eagle-import") (part "resistor_R-US_R0805"))
    )
    (comp (ref "R20")
      (value "10k")
      (footprint "eagle-import:R0805")
      (libsource (lib "eagle-import") (part "resistor_R-US_R0805"))
    )
    (comp (ref "R31")
      (value "1k")
      (footprint "eagle-import:R0805")
      (libsource (lib "eagle-import") (part "resistor_R-US_R0805"))
    )
    (comp (ref "R32")
      (value "4.7k")
      (footprint "eagle-import:R0805")
      (libsource (lib "eagle-import") (part "resistor_R-US_R0805"))
    )
    (comp (ref "R44")
      (value "R-US_R0805")
      (footprint "eagle-import:R0805")
      (libsource (lib "eagle-import") (part "resistor_R-US_R0805"))
    )
    (comp (ref "R45")
      (value "R-US_R0805")
      (footprint "eagle-import:R0805")
      (libsource (lib "eagle-import") (part "resistor_R-US_R0805"))
    )
    (comp (ref "R46")
      (value "R-US_R0805")
      (footprint "eagle-import:R0805")
      (libsource (lib "eagle-import") (part "resistor_R-US_R0805"))
    )
    (comp (ref "R47")
      (value "R-US_R0805")
      (footprint "eagle-import:R0805")
      (libsource (lib "eagle-import") (part "resistor_R-US_R0805"))
    )
    (comp (ref "S3")
      (value "TAC_SWITCHPTH")
      (footprint "eagle-import:TACTILE-PTH")
      (libsource (lib "eagle-import") (part "TAC_SWITCHPTH"))
    )
    (comp (ref "SJ1")
      (value "SOLDERJUMPERTRACE")
      (footprint "eagle-import:SJ_2S-TRACE")
      (libsource (lib "eagle-import") (part "SOLDERJUMPERTRACE"))
    )
    (comp (ref "T2")
      (value "NTE0505MC")
      (footprint "eagle-import:SO-8FT")
      (libsource (lib "eagle-import") (part "NTE0505MC"))
    )
    (comp (ref "U$16")
      (value "TCMT1103-OPTO")
      (footprint "eagle-import:SSOP-4")
      (libsource (lib "eagle-import") (part "TCMT1103-OPTO"))
    )
    (comp (ref "U$17")
      (value "TCMT1103-OPTO")
      (footprint "eagle-import:SSOP-4")
      (libsource (lib "eagle-import") (part "TCMT1103-OPTO"))
    )
    (comp (ref "U$18")
      (value "TCMT1103-OPTO")
      (footprint "eagle-import:SSOP-4")
      (libsource (lib "eagle-import") (part "TCMT1103-OPTO"))
    )
    (comp (ref "U$19")
      (value "TCMT1103-OPTO")
      (footprint "eagle-import:SSOP-4")
      (libsource (lib "eagle-import") (part "TCMT1103-OPTO"))
    )
    (comp (ref "U3")
      (value "ATMEGA328")
      (footprint "eagle-import:TQFP32-08")
      (libsource (lib "eagle-import") (part "ATMEGA168"))
    )
    (comp (ref "U5")
      (value "IL715")
      (footprint "eagle-import:S016")
      (libsource (lib "eagle-import") (part "IL715"))
    )
    (comp (ref "U6")
      (value "IL715")
      (footprint "eagle-import:S016")
      (libsource (lib "eagle-import") (part "IL715"))
    )
    (comp (ref "U7")
      (value "MCP73831")
      (footprint "eagle-import:SOT23-5")
      (libsource (lib "eagle-import") (part "MCP73831"))
    )
    (comp (ref "U9")
      (value "MAX17043G+U")
      (footprint "eagle-import:TDFN-8")
      (libsource (lib "eagle-import") (part "MAX1704X"))
    )
    (comp (ref "U20")
      (value "MAX823")
      (footprint "eagle-import:SOT23-5L")
      (libsource (lib "eagle-import") (part "MAX823"))
    )
    (comp (ref "VREG")
      (value "MIC5205-3.3V")
      (footprint "eagle-import:SOT23-5")
      (libsource (lib "eagle-import") (part "V_REG_LDOSMD"))
    )
    (comp (ref "X4")
      (value "CERMOSCILL-AWCSR")
      (footprint "eagle-import:AWCSR")
      (libsource (lib "eagle-import") (part "CERMOSCILL-AWCSR"))
    )
    (comp (ref "C26")
      (value "10uF")
      (footprint "eagle-import:EIA3216-KIT")
      (libsource (lib "eagle-import") (part "CAP_POL1206-KIT"))
    )
    (comp (ref "C27")
      (value "0.1uF")
      (footprint "eagle-import:C0805")
      (libsource (lib "eagle-import") (part "C-USC0805"))
    )
    (comp (ref "C28")
      (value "10uF")
      (footprint "eagle-import:EIA3216-KIT")
      (libsource (lib "eagle-import") (part "CAP_POL1206-KIT"))
    )
    (comp (ref "C29")
      (value "0.1uF")
      (footprint "eagle-import:C0805")
      (libsource (lib "eagle-import") (part "C-USC0805"))
    )
    (comp (ref "JP17")
      (value "M04POLAR")
      (footprint "eagle-import:MOLEX-1X4")
      (libsource (lib "eagle-import") (part "M04POLAR"))
    )
    (comp (ref "JP18")
      (value "M04POLAR")
      (footprint "eagle-import:MOLEX-1X4")
      (libsource (lib "eagle-import") (part "M04POLAR"))
    )
    (comp (ref "U11")
      (value "ADS1015")
      (footprint "eagle-import:MSOP-10")
      (libsource (lib "eagle-import") (part "ADS1015"))
    )
    (comp (ref "U13")
      (value "ADS1015")
      (footprint "eagle-import:MSOP-10")
      (libsource (lib "eagle-import") (part "ADS1015"))
    )
  )
  (nets
    (net (code "1") (name "+3V3") (class "Default")
      (node (ref "3.3V") (pin "2") (pinfunction "2_2") (pintype "passive"))
      (node (ref "C1") (pin "+") (pinfunction "+_+") (pintype "passive"))
      (node (ref "C26") (pin "A") (pinfunction "+_A") (pintype "passive"))
      (node (ref "C27") (pin "1") (pinfunction "1_1") (pintype "passive"))
      (node (ref "C28") (pin "A") (pinfunction "+_A") (pintype "passive"))
      (node (ref "C29") (pin "1") (pinfunction "1_1") (pintype "passive"))
      (node (ref "C34") (pin "1") (pinfunction "1_1") (pintype "passive"))
      (node (ref "C7") (pin "1") (pinfunction "1_1") (pintype "passive"))
      (node (ref "C8") (pin "A") (pinfunction "+_A") (pintype "passive"))
      (node (ref "J4") (pin "2") (pinfunction "2_2") (pintype "passive"))
      (node (ref "JP11") (pin "4") (pinfunction "4_4") (pintype "passive"))
      (node (ref "JP3") (pin "5") (pinfunction "5_5") (pintype "passive"))
      (node (ref "Q11") (pin "1") (pinfunction "G_1") (pintype "passive"))
      (node (ref "Q12") (pin "1") (pinfunction "G_1") (pintype "passive"))
      (node (ref "Q13") (pin "1") (pinfunction "G_1") (pintype "passive"))
      (node (ref "Q14") (pin "1") (pinfunction "G_1") (pintype "passive"))
      (node (ref "R11") (pin "1") (pinfunction "1_1") (pintype "passive"))
      (node (ref "R22") (pin "2") (pinfunction "2_2") (pintype "passive"))
      (node (ref "R24") (pin "2") (pinfunction "2_2") (pintype "passive"))
      (node (ref "R39") (pin "2") (pinfunction "2_2") (pintype "passive"))
      (node (ref "R43") (pin "2") (pinfunction "2_2") (pintype "passive"))
      (node (ref "R5") (pin "1") (pinfunction "1_1") (pintype "passive"))
      (node (ref "R6") (pin "1") (pinfunction "1_1") (pintype "passive"))
      (node (ref "R7") (pin "1") (pinfunction "1_1") (pintype "passive"))
      (node (ref "SJ3") (pin "1") (pinfunction "1_1") (pintype "passive"))
      (node (ref "SJ6") (pin "3") (pinfunction "3_3") (pintype "passive"))
      (node (ref "U1") (pin "37") (pinfunction "3.3V_37") (pintype "bidirectional"))
      (node (ref "U11") (pin "8") (pinfunction "VDD_8") (pintype "bidirectional"))
      (node (ref "U12") (pin "13") (pinfunction "VDD_13") (pintype "bidirectional"))
      (node (ref "U13") (pin "8") (pinfunction "VDD_8") (pintype "bidirectional"))
    )
    (net (code "2") (name "+9V") (class "Default")
      (node (ref "9V") (pin "2") (pinfunction "2_2") (pintype "passive"))
      (node (ref "C3") (pin "+") (pinfunction "+_+") (pintype "passive"))
      (node (ref "C36") (pin "+") (pinfunction "+_+") (pintype "passive"))
      (node (ref "J4") (pin "4") (pinfunction "4_4") (pintype "passive"))
      (node (ref "JP11") (pin "2") (pinfunction "2_2") (pintype "passive"))
      (node (ref "Q16") (pin "4") (pinfunction "D_4") (pintype "passive"))
      (node (ref "R12") (pin "1") (pinfunction "1_1") (pintype "passive"))
      (node (ref "U15") (pin "1") (pinfunction "V+_1") (pintype "bidirectional"))
    )
    (net (code "3") (name "+12V") (class "Default")
      (node (ref "12V") (pin "2") (pinfunction "2_2") (pintype "passive"))
      (node (ref "C4") (pin "+") (pinfunction "+_+") (pintype "passive"))
      (node (ref "F1") (pin "1") (pinfunction "1_1") (pintype "passive"))
      (node (ref "F2") (pin "1") (pinfunction "1_1") (pintype "passive"))
      (node (ref "F3") (pin "1") (pinfunction "1_1") (pintype "passive"))
      (node (ref "J4") (pin "5") (pinfunction "5_5") (pintype "passive"))
      (node (ref "JP11") (pin "1") (pinfunction "1_1") (pintype "passive"))
      (node (ref "R21") (pin "1") (pinfunction "1_1") (pintype "passive"))
    )
    (net (code "4") (name "3.3VEN") (class "Default")
      (node (ref "JP8") (pin "4") (pinfunction "4_4") (pintype "passive"))
      (node (ref "U$16") (pin "4") (pinfunction "C_4") (pintype "bidirectional"))
    )
    (net (code "5") (name "3V3SCL") (class "Default")
      (node (ref "Q11") (pin "2") (pinfunction "S_2") (pintype "passive"))
      (node (ref "R43") (pin "1") (pinfunction "1_1") (pintype "passive"))
      (node (ref "U12") (pin "23") (pinfunction "SCL_23") (pintype "bidirectional"))
    )
    (net (code "6") (name "3V3SDA") (class "Default")
      (node (ref "Q12") (pin "2") (pinfunction "S_2") (pintype "passive"))
      (node (ref "R39") (pin "1") (pinfunction "1_1") (pintype "passive"))
      (node (ref "U12") (pin "24") (pinfunction "SDA_24") (pintype "bidirectional"))
    )
    (net (code "7") (name "5V") (class "Default")
      (node (ref "5V") (pin "2") (pinfunction "2_2") (pintype "passive"))
      (node (ref "C2") (pin "+") (pinfunction "+_+") (pintype "passive"))
      (node (ref "C24") (pin "+") (pinfunction "+_+") (pintype "passive"))
      (node (ref "C30") (pin "1") (pinfunction "1_1") (pintype "passive"))
      (node (ref "C31") (pin "1") (pinfunction "1_1") (pintype "passive"))
      (node (ref "C38") (pin "1") (pinfunction "1_1") (pintype "passive"))
      (node (ref "C39") (pin "1") (pinfunction "1_1") (pintype "passive"))
      (node (ref "CHG") (pin "2") (pinfunction "P_2") (pintype "passive"))
      (node (ref "J4") (pin "3") (pinfunction "3_3") (pintype "passive"))
      (node (ref "J5") (pin "11") (pinfunction "11_11") (pintype "passive"))
      (node (ref "J5") (pin "4") (pinfunction "4_4") (pintype "passive"))
      (node (ref "J5") (pin "5") (pinfunction "5_5") (pintype "passive"))
      (node (ref "J5") (pin "6") (pinfunction "6_6") (pintype "passive"))
      (node (ref "J5") (pin "7") (pinfunction "7_7") (pintype "passive"))
      (node (ref "J5") (pin "8") (pinfunction "8_8") (pintype "passive"))
      (node (ref "JP11") (pin "3") (pinfunction "3_3") (pintype "passive"))
      (node (ref "JP3") (pin "4") (pinfunction "4_4") (pintype "passive"))
      (node (ref "Q10") (pin "4") (pinfunction "D_4") (pintype "passive"))
      (node (ref "Q15") (pin "1") (pinfunction "S_1") (pintype "bidirectional"))
      (node (ref "Q15") (pin "2") (pinfunction "S_2") (pintype "bidirectional"))
      (node (ref "Q15") (pin "3") (pinfunction "S_3") (pintype "bidirectional"))
      (node (ref "R1") (pin "1") (pinfunction "1_1") (pintype "passive"))
      (node (ref "R10") (pin "1") (pinfunction "1_1") (pintype "passive"))
      (node (ref "R23") (pin "2") (pinfunction "2_2") (pintype "passive"))
      (node (ref "R27") (pin "2") (pinfunction "2_2") (pintype "passive"))
      (node (ref "R38") (pin "2") (pinfunction "2_2") (pintype "passive"))
      (node (ref "R42") (pin "2") (pinfunction "2_2") (pintype "passive"))
      (node (ref "SJ6") (pin "1") (pinfunction "1_1") (pintype "passive"))
      (node (ref "U10") (pin "1") (pinfunction "V+_1") (pintype "bidirectional"))
      (node (ref "U16") (pin "16") (pinfunction "VCC_16") (pintype "bidirectional"))
      (node (ref "U2") (pin "28") (pinfunction "VDD_28") (pintype "power_in"))
      (node (ref "U47") (pin "20") (pinfunction "VCC_20") (pintype "bidirectional"))
      (node (ref "U49") (pin "20") (pinfunction "VCC_20") (pintype "bidirectional"))
      (node (ref "U5") (pin "1") (pinfunction "VDD1_1") (pintype "bidirectional"))
      (node (ref "U6") (pin "16") (pinfunction "VDD2_16") (pintype "bidirectional"))
    )
    (net (code "8") (name "5VEN") (class "Default")
      (node (ref "JP8") (pin "3") (pinfunction "3_3") (pintype "passive"))
      (node (ref "U$18") (pin "4") (pinfunction "C_4") (pintype "bidirectional"))
    )
    (net (code "9") (name "9VEN") (class "Default")
      (node (ref "JP8") (pin "1") (pinfunction "1_1") (pintype "passive"))
      (node (ref "U$17") (pin "4") (pinfunction "C_4") (pintype "bidirectional"))
    )
    (net (code "10") (name "12VEN") (class "Default")
      (node (ref "JP8") (pin "2") (pinfunction "2_2") (pintype "passive"))
      (node (ref "U$19") (pin "4") (pinfunction "C_4") (pintype "bidirectional"))
    )
    (net (code "11") (name "AD0") (class "Default")
      (node (ref "SJ3") (pin "2") (pinfunction "2_2") (pintype "passive"))
      (node (ref "U12") (pin "9") (pinfunction "AD0_9") (pintype "bidirectional"))
    )
    (net (code "12") (name "ADC0") (class "Default")
      (node (ref "IC2") (pin "97") (pinfunction "(ADC0)PF0_97") (pintype "bidirectional"))
      (node (ref "J5") (pin "12") (pinfunction "12_12") (pintype "passive"))
    )
    (net (code "13") (name "ADC1") (class "Default")
      (node (ref "IC2") (pin "96") (pinfunction "(ADC1)PF1_96") (pintype "bidirectional"))
      (node (ref "J5") (pin "13") (pinfunction "13_13") (pintype "passive"))
    )
    (net (code "14") (name "ADC2") (class "Default")
      (node (ref "IC2") (pin "95") (pinfunction "(ADC2)PF2_95") (pintype "bidirectional"))
      (node (ref "J5") (pin "14") (pinfunction "14_14") (pintype "passive"))
    )
    (net (code "15") (name "ADC3") (class "Default")
      (node (ref "IC2") (pin "94") (pinfunction "(ADC3)PF3_94") (pintype "bidirectional"))
      (node (ref "J5") (pin "15") (pinfunction "15_15") (pintype "passive"))
    )
    (net (code "16") (name "ADC4") (class "Default")
      (node (ref "IC2") (pin "93") (pinfunction "(ADC4/TCK)PF4_93") (pintype "bidirectional"))
      (node (ref "J5") (pin "16") (pinfunction "16_16") (pintype "passive"))
    )
    (net (code "17") (name "ADC5") (class "Default")
      (node (ref "IC2") (pin "92") (pinfunction "(ADC5/TMS)PF5_92") (pintype "bidirectional"))
      (node (ref "J6") (pin "9") (pinfunction "9_9") (pintype "passive"))
    )
    (net (code "18") (name "ADC6") (class "Default")
      (node (ref "IC2") (pin "91") (pinfunction "(ADC6/TDO)PF6_91") (pintype "bidirectional"))
      (node (ref "J6") (pin "10") (pinfunction "10_10") (pintype "passive"))
    )
    (net (code "19") (name "ADC7") (class "Default")
      (node (ref "IC2") (pin "90") (pinfunction "(ADC7/TDI)PF7_90") (pintype "bidirectional"))
      (node (ref "J6") (pin "11") (pinfunction "11_11") (pintype "passive"))
    )
    (net (code "20") (name "ADC8") (class "Default")
      (node (ref "IC2") (pin "89") (pinfunction "PK0(ADC8/PCINT16)_89") (pintype "bidirectional"))
      (node (ref "J6") (pin "12") (pinfunction "12_12") (pintype "passive"))
    )
    (net (code "21") (name "ADC9") (class "Default")
      (node (ref "IC2") (pin "88") (pinfunction "PK1(ADC9/PCINT17)_88") (pintype "bidirectional"))
      (node (ref "J6") (pin "13") (pinfunction "13_13") (pintype "passive"))
    )
    (net (code "22") (name "ALT") (class "Default")
      (node (ref "SJ1") (pin "1") (pinfunction "1_1") (pintype "passive"))
      (node (ref "U9") (pin "5") (pinfunction "ALT_5") (pintype "bidirectional"))
    )
    (net (code "23") (name "AUX_SCL") (class "Default")
      (node (ref "U12") (pin "7") (pinfunction "AUX_CL_7") (pintype "bidirectional"))
    )
    (net (code "24") (name "AUX_SDA") (class "Default")
      (node (ref "U12") (pin "6") (pinfunction "AUX_DA_6") (pintype "bidirectional"))
    )
    (net (code "25") (name "AVRPWR") (class "Default")
      (node (ref "C16") (pin "1") (pinfunction "1_1") (pintype "passive"))
      (node (ref "C17") (pin "1") (pinfunction "1_1") (pintype "passive"))
      (node (ref "C18") (pin "1") (pinfunction "1_1") (pintype "passive"))
      (node (ref "C19") (pin "1") (pinfunction "1_1") (pintype "passive"))
      (node (ref "IC2") (pin "10") (pinfunction "VCC_10") (pintype "power_in"))
      (node (ref "IC2") (pin "100") (pinfunction "AVCC_100") (pintype "power_in"))
      (node (ref "IC2") (pin "31") (pinfunction "VCC1_31") (pintype "power_in"))
      (node (ref "IC2") (pin "61") (pinfunction "VCC2_61") (pintype "power_in"))
      (node (ref "IC2") (pin "80") (pinfunction "VCC3_80") (pintype "power_in"))
      (node (ref "ICSP") (pin "2") (pinfunction "2_2") (pintype "passive"))
      (node (ref "Q15") (pin "5") (pinfunction "D_5") (pintype "bidirectional"))
      (node (ref "Q15") (pin "6") (pinfunction "D_6") (pintype "bidirectional"))
      (node (ref "Q15") (pin "7") (pinfunction "D_7") (pintype "bidirectional"))
      (node (ref "Q15") (pin "8") (pinfunction "D_8") (pintype "bidirectional"))
      (node (ref "R26") (pin "2") (pinfunction "2_2") (pintype "passive"))
      (node (ref "R34") (pin "2") (pinfunction "2_2") (pintype "passive"))
      (node (ref "R35") (pin "2") (pinfunction "2_2") (pintype "passive"))
      (node (ref "R36") (pin "2") (pinfunction "2_2") (pintype "passive"))
      (node (ref "R37") (pin "2") (pinfunction "2_2") (pintype "passive"))
      (node (ref "R40") (pin "1") (pinfunction "1_1") (pintype "passive"))
      (node (ref "R41") (pin "1") (pinfunction "1_1") (pintype "passive"))
    )
    (net (code "26") (name "CLKIN") (class "Default")
      (node (ref "SJ5") (pin "2") (pinfunction "2_2") (pintype "passive"))
      (node (ref "U12") (pin "1") (pinfunction "CLKIN_1") (pintype "bidirectional"))
    )
    (net (code "27") (name "D2") (class "Default")
      (node (ref "SJ1") (pin "2") (pinfunction "2_2") (pintype "passive"))
      (node (ref "U3") (pin "32") (pinfunction "PD2(INT0)_32") (pintype "bidirectional"))
    )
    (net (code "28") (name "ETHCONECT") (class "Default")
      (node (ref "ELINK") (pin "C") (pinfunction "C_C") (pintype "passive"))
      (node (ref "U1") (pin "18") (pinfunction "ELED1_18") (pintype "bidirectional"))
    )
    (net (code "29") (name "FSYNC") (class "Default")
      (node (ref "SJ4") (pin "2") (pinfunction "2_2") (pintype "passive"))
      (node (ref "U12") (pin "11") (pinfunction "FSYNC_11") (pintype "bidirectional"))
    )
    (net (code "30") (name "GND") (class "Default")
      (node (ref "12V") (pin "1") (pinfunction "1_1") (pintype "passive"))
      (node (ref "12V\\") (pin "C") (pinfunction "C_C") (pintype "passive"))
      (node (ref "13") (pin "C") (pinfunction "C_C") (pintype "passive"))
      (node (ref "3.3V") (pin "1") (pinfunction "1_1") (pintype "passive"))
      (node (ref "3.3V\\") (pin "C") (pinfunction "C_C") (pintype "passive"))
      (node (ref "5V") (pin "1") (pinfunction "1_1") (pintype "passive"))
      (node (ref "5V\\") (pin "C") (pinfunction "C_C") (pintype "passive"))
      (node (ref "9V") (pin "1") (pinfunction "1_1") (pintype "passive"))
      (node (ref "9V\\") (pin "C") (pinfunction "C_C") (pintype "passive"))
      (node (ref "C1") (pin "-") (pinfunction "-_-") (pintype "passive"))
      (node (ref "C10") (pin "C") (pinfunction "-_C") (pintype "passive"))
      (node (ref "C16") (pin "2") (pinfunction "2_2") (pintype "passive"))
      (node (ref "C17") (pin "2") (pinfunction "2_2") (pintype "passive"))
      (node (ref "C18") (pin "2") (pinfunction "2_2") (pintype "passive"))
      (node (ref "C19") (pin "2") (pinfunction "2_2") (pintype "passive"))
      (node (ref "C2") (pin "-") (pinfunction "-_-") (pintype "passive"))
      (node (ref "C20") (pin "2") (pinfunction "2_2") (pintype "passive"))
      (node (ref "C24") (pin "-") (pinfunction "-_-") (pintype "passive"))
      (node (ref "C26") (pin "C") (pinfunction "-_C") (pintype "passive"))
      (node (ref "C27") (pin "2") (pinfunction "2_2") (pintype "passive"))
      (node (ref "C28") (pin "C") (pinfunction "-_C") (pintype "passive"))
      (node (ref "C29") (pin "2") (pinfunction "2_2") (pintype "passive"))
      (node (ref "C3") (pin "-") (pinfunction "-_-") (pintype "passive"))
      (node (ref "C30") (pin "2") (pinfunction "2_2") (pintype "passive"))
      (node (ref "C31") (pin "2") (pinfunction "2_2") (pintype "passive"))
      (node (ref "C32") (pin "2") (pinfunction "2_2") (pintype "passive"))
      (node (ref "C33") (pin "2") (pinfunction "2_2") (pintype "passive"))
      (node (ref "C34") (pin "2") (pinfunction "2_2") (pintype "passive"))
      (node (ref "C35") (pin "2") (pinfunction "2_2") (pintype "passive"))
      (node (ref "C36") (pin "-") (pinfunction "-_-") (pintype "passive"))
      (node (ref "C38") (pin "2") (pinfunction "2_2") (pintype "passive"))
      (node (ref "C39") (pin "2") (pinfunction "2_2") (pintype "passive"))
      (node (ref "C4") (pin "-") (pinfunction "-_-") (pintype "passive"))
      (node (ref "C5") (pin "2") (pinfunction "2_2") (pintype "passive"))
      (node (ref "C6") (pin "2") (pinfunction "2_2") (pintype "passive"))
      (node (ref "C7") (pin "2") (pinfunction "2_2") (pintype "passive"))
      (node (ref "C8") (pin "C") (pinfunction "-_C") (pintype "passive"))
      (node (ref "C9") (pin "1") (pinfunction "1_1") (pintype "passive"))
      (node (ref "CN1") (pin "GND") (pinfunction "GND_GND") (pintype "power_in"))
      (node (ref "H10") (pin "B2,8") (pinfunction "MOUNT_B2,8") (pintype "passive"))
      (node (ref "H2") (pin "B2,8") (pinfunction "MOUNT_B2,8") (pintype "passive"))
      (node (ref "H4") (pin "B2,8") (pinfunction "MOUNT_B2,8") (pintype "passive"))
      (node (ref "H5") (pin "B2,8") (pinfunction "MOUNT_B2,8") (pintype "passive"))
      (node (ref "H6") (pin "B2,8") (pinfunction "MOUNT_B2,8") (pintype "passive"))
      (node (ref "IC1") (pin "18") (pinfunction "GND_18") (pintype "power_in"))
      (node (ref "IC1") (pin "21") (pinfunction "GND_21") (pintype "power_in"))
      (node (ref "IC1") (pin "25") (pinfunction "GND_25") (pintype "power_in"))
      (node (ref "IC1") (pin "26") (pinfunction "TEST_26") (pintype "input"))
      (node (ref "IC1") (pin "7") (pinfunction "GND_7") (pintype "power_in"))
      (node (ref "IC2") (pin "11") (pinfunction "GND_11") (pintype "power_in"))
      (node (ref "IC2") (pin "32") (pinfunction "GND1_32") (pintype "power_in"))
      (node (ref "IC2") (pin "62") (pinfunction "GND2_62") (pintype "power_in"))
      (node (ref "IC2") (pin "81") (pinfunction "GND3_81") (pintype "power_in"))
      (node (ref "IC2") (pin "99") (pinfunction "AGND_99") (pintype "power_in"))
      (node (ref "ICSP") (pin "6") (pinfunction "6_6") (pintype "passive"))
      (node (ref "J4") (pin "10") (pinfunction "10_10") (pintype "passive"))
      (node (ref "J4") (pin "6") (pinfunction "6_6") (pintype "passive"))
      (node (ref "J4") (pin "7") (pinfunction "7_7") (pintype "passive"))
      (node (ref "J4") (pin "8") (pinfunction "8_8") (pintype "passive"))
      (node (ref "J4") (pin "9") (pinfunction "9_9") (pintype "passive"))
      (node (ref "J6") (pin "14") (pinfunction "14_14") (pintype "passive"))
      (node (ref "J6") (pin "15") (pinfunction "15_15") (pintype "passive"))
      (node (ref "J6") (pin "16") (pinfunction "16_16") (pintype "passive"))
      (node (ref "J6") (pin "6") (pinfunction "6_6") (pintype "passive"))
      (node (ref "J6") (pin "7") (pinfunction "7_7") (pintype "passive"))
      (node (ref "J6") (pin "8") (pinfunction "8_8") (pintype "passive"))
      (node (ref "J7") (pin "1") (pinfunction "1_1") (pintype "passive"))
      (node (ref "J7") (pin "2") (pinfunction "2_2") (pintype "passive"))
      (node (ref "J7") (pin "3") (pinfunction "3_3") (pintype "passive"))
      (node (ref "J7") (pin "4") (pinfunction "4_4") (pintype "passive"))
      (node (ref "J7") (pin "5") (pinfunction "5_5") (pintype "passive"))
      (node (ref "J7") (pin "6") (pinfunction "6_6") (pintype "passive"))
      (node (ref "J7") (pin "7") (pinfunction "7_7") (pintype "passive"))
      (node (ref "J7") (pin "8") (pinfunction "8_8") (pintype "passive"))
      (node (ref "J8") (pin "1") (pinfunction "1_1") (pintype "passive"))
      (node (ref "J8") (pin "2") (pinfunction "2_2") (pintype "passive"))
      (node (ref "J8") (pin "3") (pinfunction "3_3") (pintype "passive"))
      (node (ref "J8") (pin "4") (pinfunction "4_4") (pintype "passive"))
      (node (ref "J8") (pin "5") (pinfunction "5_5") (pintype "passive"))
      (node (ref "J8") (pin "6") (pinfunction "6_6") (pintype "passive"))
      (node (ref "J8") (pin "8") (pinfunction "8_8") (pintype "passive"))
      (node (ref "JP1") (pin "3") (pinfunction "3_3") (pintype "passive"))
      (node (ref "JP10") (pin "1") (pinfunction "1_1") (pintype "passive"))
      (node (ref "JP3") (pin "3") (pinfunction "3_3") (pintype "passive"))
      (node (ref "LANNAS") (pin "1") (pinfunction "1_1") (pintype "passive"))
      (node (ref "MCS") (pin "3") (pinfunction "3_3") (pintype "passive"))
      (node (ref "NAS") (pin "1") (pinfunction "1_1") (pintype "passive"))
      (node (ref "NAS3V") (pin "1") (pinfunction "1_1") (pintype "passive"))
      (node (ref "OSS") (pin "2") (pinfunction "GND_2") (pintype "bidirectional"))
      (node (ref "Q1") (pin "3") (pinfunction "S_3") (pintype "passive"))
      (node (ref "Q2") (pin "3") (pinfunction "S_3") (pintype "passive"))
      (node (ref "Q3") (pin "3") (pinfunction "S_3") (pintype "passive"))
      (node (ref "Q4") (pin "3") (pinfunction "S_3") (pintype "passive"))
      (node (ref "Q5") (pin "3") (pinfunction "S_3") (pintype "passive"))
      (node (ref "Q6") (pin "3") (pinfunction "S_3") (pintype "passive"))
      (node (ref "Q7") (pin "3") (pinfunction "S_3") (pintype "passive"))
      (node (ref "Q8") (pin "3") (pinfunction "S_3") (pintype "passive"))
      (node (ref "Q9") (pin "3") (pinfunction "S_3") (pintype "passive"))
      (node (ref "R28") (pin "2") (pinfunction "2_2") (pintype "passive"))
      (node (ref "R29") (pin "2") (pinfunction "2_2") (pintype "passive"))
      (node (ref "RASPBERRYPI") (pin "11") (pinfunction "11_11") (pintype "passive"))
      (node (ref "S1") (pin "3") (pinfunction "3_3") (pintype "passive"))
      (node (ref "S1") (pin "4") (pinfunction "4_4") (pintype "passive"))
      (node (ref "SJ3") (pin "3") (pinfunction "3_3") (pintype "passive"))
      (node (ref "SJ4") (pin "1") (pinfunction "1_1") (pintype "passive"))
      (node (ref "SJ5") (pin "1") (pinfunction "1_1") (pintype "passive"))
      (node (ref "T2") (pin "1") (pinfunction "2_1") (pintype "passive"))
      (node (ref "U$16") (pin "3") (pinfunction "E_3") (pintype "bidirectional"))
      (node (ref "U$17") (pin "3") (pinfunction "E_3") (pintype "bidirectional"))
      (node (ref "U$18") (pin "3") (pinfunction "E_3") (pintype "bidirectional"))
      (node (ref "U$19") (pin "3") (pinfunction "E_3") (pintype "bidirectional"))
      (node (ref "U1") (pin "2") (pinfunction "GND_2") (pintype "bidirectional"))
      (node (ref "U1") (pin "39") (pinfunction "GND_39") (pintype "bidirectional"))
      (node (ref "U10") (pin "4") (pinfunction "GND_4") (pintype "bidirectional"))
      (node (ref "U11") (pin "3") (pinfunction "GND_3") (pintype "bidirectional"))
      (node (ref "U12") (pin "18") (pinfunction "GND_18") (pintype "bidirectional"))
      (node (ref "U13") (pin "3") (pinfunction "GND_3") (pintype "bidirectional"))
      (node (ref "U15") (pin "4") (pinfunction "GND_4") (pintype "bidirectional"))
      (node (ref "U16") (pin "6") (pinfunction "~{E}_6") (pintype "bidirectional"))
      (node (ref "U16") (pin "7") (pinfunction "VEE_7") (pintype "bidirectional"))
      (node (ref "U16") (pin "8") (pinfunction "GND_8") (pintype "bidirectional"))
      (node (ref "U2") (pin "1") (pinfunction "A0_1") (pintype "bidirectional"))
      (node (ref "U2") (pin "14") (pinfunction "GND_14") (pintype "power_in"))
      (node (ref "U2") (pin "2") (pinfunction "A1_2") (pintype "bidirectional"))
      (node (ref "U2") (pin "23") (pinfunction "#OE_23") (pintype "input"))
      (node (ref "U2") (pin "24") (pinfunction "A5_24") (pintype "bidirectional"))
      (node (ref "U2") (pin "25") (pinfunction "EXTCLK_25") (pintype "input"))
      (node (ref "U2") (pin "3") (pinfunction "A2_3") (pintype "bidirectional"))
      (node (ref "U2") (pin "4") (pinfunction "A3_4") (pintype "bidirectional"))
      (node (ref "U2") (pin "5") (pinfunction "A4_5") (pintype "bidirectional"))
      (node (ref "U47") (pin "1") (pinfunction "EN_1") (pintype "bidirectional"))
      (node (ref "U47") (pin "10") (pinfunction "GND_10") (pintype "bidirectional"))
      (node (ref "U49") (pin "1") (pinfunction "EN_1") (pintype "bidirectional"))
      (node (ref "U49") (pin "10") (pinfunction "GND_10") (pintype "bidirectional"))
      (node (ref "U5") (pin "2") (pinfunction "GND1_2") (pintype "bidirectional"))
      (node (ref "U5") (pin "8") (pinfunction "GND1_8") (pintype "bidirectional"))
      (node (ref "U6") (pin "15") (pinfunction "GND2_15") (pintype "bidirectional"))
      (node (ref "U6") (pin "9") (pinfunction "GND2_9") (pintype "bidirectional"))
      (node (ref "USB") (pin "3") (pinfunction "3_3") (pintype "passive"))
    )
    (net (code "31") (name "GNDIO") (class "Default")
      (node (ref "C11") (pin "2") (pinfunction "2_2") (pintype "passive"))
      (node (ref "C12") (pin "-") (pinfunction "-_-") (pintype "passive"))
      (node (ref "C13") (pin "-") (pinfunction "-_-") (pintype "passive"))
      (node (ref "C14") (pin "2") (pinfunction "2_2") (pintype "passive"))
      (node (ref "C15") (pin "2") (pinfunction "2_2") (pintype "passive"))
      (node (ref "C21") (pin "2") (pinfunction "2_2") (pintype "passive"))
      (node (ref "C22") (pin "2") (pinfunction "2_2") (pintype "passive"))
      (node (ref "C23") (pin "-") (pinfunction "-_-") (pintype "passive"))
      (node (ref "C25") (pin "2") (pinfunction "2_2") (pintype "passive"))
      (node (ref "ISP1") (pin "6") (pinfunction "GND_6") (pintype "power_in"))
      (node (ref "JP4") (pin "2") (pinfunction "2_2") (pintype "passive"))
      (node (ref "JP6") (pin "1") (pinfunction "1_1") (pintype "passive"))
      (node (ref "LED1") (pin "C") (pinfunction "C_C") (pintype "passive"))
      (node (ref "R20") (pin "1") (pinfunction "1_1") (pintype "passive"))
      (node (ref "R32") (pin "1") (pinfunction "1_1") (pintype "passive"))
      (node (ref "S3") (pin "1") (pinfunction "1_1") (pintype "passive"))
      (node (ref "S3") (pin "2") (pinfunction "2_2") (pintype "passive"))
      (node (ref "T2") (pin "7") (pinfunction "3_7") (pintype "passive"))
      (node (ref "U$16") (pin "2") (pinfunction "K_2") (pintype "bidirectional"))
      (node (ref "U$17") (pin "2") (pinfunction "K_2") (pintype "bidirectional"))
      (node (ref "U$18") (pin "2") (pinfunction "K_2") (pintype "bidirectional"))
      (node (ref "U$19") (pin "2") (pinfunction "K_2") (pintype "bidirectional"))
      (node (ref "U20") (pin "2") (pinfunction "GND_2") (pintype "bidirectional"))
      (node (ref "U3") (pin "21") (pinfunction "GND_21") (pintype "bidirectional"))
      (node (ref "U3") (pin "3") (pinfunction "GND_3") (pintype "bidirectional"))
      (node (ref "U3") (pin "5") (pinfunction "AGND_5") (pintype "bidirectional"))
      (node (ref "U5") (pin "15") (pinfunction "GND2_15") (pintype "bidirectional"))
      (node (ref "U5") (pin "9") (pinfunction "GND2_9") (pintype "bidirectional"))
      (node (ref "U6") (pin "2") (pinfunction "GND1_2") (pintype "bidirectional"))
      (node (ref "U6") (pin "8") (pinfunction "GND1_8") (pintype "bidirectional"))
      (node (ref "U7") (pin "2") (pinfunction "VSS_2") (pintype "power_in"))
      (node (ref "U9") (pin "1") (pinfunction "CTG_1") (pintype "bidirectional"))
      (node (ref "U9") (pin "4") (pinfunction "GND_4") (pintype "bidirectional"))
      (node (ref "U9") (pin "EP") (pinfunction "GND_EP") (pintype "bidirectional"))
      (node (ref "VREG") (pin "2") (pinfunction "GND_2") (pintype "input"))
      (node (ref "X4") (pin "2") (pinfunction "GND_2") (pintype "bidirectional"))
    )
    (net (code "32") (name "IN1") (class "Default")
      (node (ref "J7") (pin "9") (pinfunction "9_9") (pintype "passive"))
      (node (ref "U47") (pin "9") (pinfunction "IN8_9") (pintype "bidirectional"))
    )
    (net (code "33") (name "IN2") (class "Default")
      (node (ref "J7") (pin "10") (pinfunction "10_10") (pintype "passive"))
      (node (ref "U47") (pin "8") (pinfunction "IN7_8") (pintype "bidirectional"))
    )
    (net (code "34") (name "IN3") (class "Default")
      (node (ref "J7") (pin "11") (pinfunction "11_11") (pintype "passive"))
      (node (ref "U47") (pin "7") (pinfunction "IN6_7") (pintype "bidirectional"))
    )
    (net (code "35") (name "IN4") (class "Default")
      (node (ref "J7") (pin "12") (pinfunction "12_12") (pintype "passive"))
      (node (ref "U47") (pin "6") (pinfunction "IN5_6") (pintype "bidirectional"))
    )
    (net (code "36") (name "IN5") (class "Default")
      (node (ref "J7") (pin "13") (pinfunction "13_13") (pintype "passive"))
      (node (ref "U47") (pin "5") (pinfunction "IN4_5") (pintype "bidirectional"))
    )
    (net (code "37") (name "IN6") (class "Default")
      (node (ref "J7") (pin "14") (pinfunction "14_14") (pintype "passive"))
      (node (ref "U47") (pin "4") (pinfunction "IN3_4") (pintype "bidirectional"))
    )
    (net (code "38") (name "IN7") (class "Default")
      (node (ref "J7") (pin "15") (pinfunction "15_15") (pintype "passive"))
      (node (ref "U47") (pin "3") (pinfunction "IN2_3") (pintype "bidirectional"))
    )
    (net (code "39") (name "IN8") (class "Default")
      (node (ref "J7") (pin "16") (pinfunction "16_16") (pintype "passive"))
      (node (ref "U47") (pin "2") (pinfunction "IN1_2") (pintype "bidirectional"))
    )
    (net (code "40") (name "IN9") (class "Default")
      (node (ref "J8") (pin "16") (pinfunction "16_16") (pintype "passive"))
      (node (ref "U49") (pin "2") (pinfunction "IN1_2") (pintype "bidirectional"))
    )
    (net (code "41") (name "IN10") (class "Default")
      (node (ref "J8") (pin "15") (pinfunction "15_15") (pintype "passive"))
      (node (ref "U49") (pin "3") (pinfunction "IN2_3") (pintype "bidirectional"))
    )
    (net (code "42") (name "IN11") (class "Default")
      (node (ref "J8") (pin "14") (pinfunction "14_14") (pintype "passive"))
      (node (ref "U49") (pin "4") (pinfunction "IN3_4") (pintype "bidirectional"))
    )
    (net (code "43") (name "IN12") (class "Default")
      (node (ref "J8") (pin "13") (pinfunction "13_13") (pintype "passive"))
      (node (ref "U49") (pin "5") (pinfunction "IN4_5") (pintype "bidirectional"))
    )
    (net (code "44") (name "IN13") (class "Default")
      (node (ref "J8") (pin "12") (pinfunction "12_12") (pintype "passive"))
      (node (ref "U49") (pin "6") (pinfunction "IN5_6") (pintype "bidirectional"))
    )
    (net (code "45") (name "IN14") (class "Default")
      (node (ref "J8") (pin "11") (pinfunction "11_11") (pintype "passive"))
      (node (ref "U49") (pin "7") (pinfunction "IN6_7") (pintype "bidirectional"))
    )
    (net (code "46") (name "IN15") (class "Default")
      (node (ref "J8") (pin "10") (pinfunction "10_10") (pintype "passive"))
      (node (ref "U49") (pin "8") (pinfunction "IN7_8") (pintype "bidirectional"))
    )
    (net (code "47") (name "IN16") (class "Default")
      (node (ref "J8") (pin "9") (pinfunction "9_9") (pintype "passive"))
      (node (ref "U49") (pin "9") (pinfunction "IN8_9") (pintype "bidirectional"))
    )
    (net (code "48") (name "INT") (class "Default")
      (node (ref "U12") (pin "12") (pinfunction "INT_12") (pintype "bidirectional"))
    )
    (net (code "49") (name "LANT1") (class "Default")
      (node (ref "R29") (pin "1") (pinfunction "1_1") (pintype "passive"))
      (node (ref "U1") (pin "13") (pinfunction "CP1_13") (pintype "bidirectional"))
      (node (ref "U16") (pin "10") (pinfunction "S0_10") (pintype "bidirectional"))
    )
    (net (code "50") (name "LANT2") (class "Default")
      (node (ref "R28") (pin "1") (pinfunction "1_1") (pintype "passive"))
      (node (ref "U1") (pin "15") (pinfunction "CP2_15") (pintype "bidirectional"))
      (node (ref "U16") (pin "9") (pinfunction "S1_9") (pintype "bidirectional"))
    )
    (net (code "51") (name "LED0") (class "Default")
      (node (ref "Q3") (pin "1") (pinfunction "G_1") (pintype "passive"))
      (node (ref "U2") (pin "6") (pinfunction "PWM0_6") (pintype "output"))
    )
    (net (code "52") (name "LED1") (class "Default")
      (node (ref "Q2") (pin "1") (pinfunction "G_1") (pintype "passive"))
      (node (ref "U2") (pin "7") (pinfunction "PWM1_7") (pintype "output"))
    )
    (net (code "53") (name "LED2") (class "Default")
      (node (ref "Q1") (pin "1") (pinfunction "G_1") (pintype "passive"))
      (node (ref "U2") (pin "8") (pinfunction "PWM2_8") (pintype "output"))
    )
    (net (code "54") (name "LED3") (class "Default")
      (node (ref "Q6") (pin "1") (pinfunction "G_1") (pintype "passive"))
      (node (ref "U2") (pin "9") (pinfunction "PWM3_9") (pintype "output"))
    )
    (net (code "55") (name "LED4") (class "Default")
      (node (ref "Q5") (pin "1") (pinfunction "G_1") (pintype "passive"))
      (node (ref "U2") (pin "10") (pinfunction "PWM4_10") (pintype "output"))
    )
    (net (code "56") (name "LED5") (class "Default")
      (node (ref "Q4") (pin "1") (pinfunction "G_1") (pintype "passive"))
      (node (ref "U2") (pin "11") (pinfunction "PWM5_11") (pintype "output"))
    )
    (net (code "57") (name "LED6") (class "Default")
      (node (ref "Q9") (pin "1") (pinfunction "G_1") (pintype "passive"))
      (node (ref "U2") (pin "12") (pinfunction "PWM6_12") (pintype "output"))
    )
    (net (code "58") (name "LED7") (class "Default")
      (node (ref "Q8") (pin "1") (pinfunction "G_1") (pintype "passive"))
      (node (ref "U2") (pin "13") (pinfunction "PWM7_13") (pintype "output"))
    )
    (net (code "59") (name "LED8") (class "Default")
      (node (ref "Q7") (pin "1") (pinfunction "G_1") (pintype "passive"))
      (node (ref "U2") (pin "15") (pinfunction "PWM8_15") (pintype "output"))
    )
    (net (code "60") (name "LHO") (class "Default")
      (node (ref "JP9") (pin "7") (pinfunction "7_7") (pintype "passive"))
    )
    (net (code "61") (name "LSU") (class "Default")
      (node (ref "JP9") (pin "6") (pinfunction "6_6") (pintype "passive"))
    )
    (net (code "62") (name "MCS") (class "Default")
      (node (ref "J5") (pin "1") (pinfunction "1_1") (pintype "passive"))
      (node (ref "U5") (pin "6") (pinfunction "IN4_6") (pintype "bidirectional"))
    )
    (net (code "63") (name "MCSPWR") (class "Default")
      (node (ref "J5") (pin "2") (pinfunction "2_2") (pintype "passive"))
      (node (ref "J5") (pin "3") (pinfunction "3_3") (pintype "passive"))
      (node (ref "Q16") (pin "3") (pinfunction "S_3") (pintype "passive"))
      (node (ref "U15") (pin "3") (pinfunction "SOURCE_3") (pintype "bidirectional"))
    )
    (net (code "64") (name "MCSRX") (class "Default")
      (node (ref "IC2") (pin "63") (pinfunction "PJ0(RXD3/PCINT9)_63") (pintype "bidirectional"))
      (node (ref "J5") (pin "9") (pinfunction "9_9") (pintype "passive"))
      (node (ref "MCS") (pin "1") (pinfunction "1_1") (pintype "passive"))
    )
    (net (code "65") (name "MCSTX") (class "Default")
      (node (ref "IC2") (pin "64") (pinfunction "PJ1(TXD3/PCINT10)_64") (pintype "bidirectional"))
      (node (ref "J5") (pin "10") (pinfunction "10_10") (pintype "passive"))
      (node (ref "MCS") (pin "2") (pinfunction "2_2") (pintype "passive"))
    )
    (net (code "66") (name "MCS_PWR") (class "Default")
      (node (ref "U15") (pin "2") (pinfunction "INPUT_2") (pintype "bidirectional"))
      (node (ref "U6") (pin "13") (pinfunction "OUT2_13") (pintype "bidirectional"))
    )
    (net (code "67") (name "MISO-1") (class "Default")
      (node (ref "IC2") (pin "22") (pinfunction "(MISO/PCINT3)PB3_22") (pintype "bidirectional"))
      (node (ref "ICSP") (pin "1") (pinfunction "1_1") (pintype "passive"))
    )
    (net (code "68") (name "MOSI-1") (class "Default")
      (node (ref "IC2") (pin "21") (pinfunction "(MOSI/PCINT2)PB2_21") (pintype "bidirectional"))
      (node (ref "ICSP") (pin "4") (pinfunction "4_4") (pintype "passive"))
    )
    (net (code "69") (name "MTEN") (class "Default")
      (node (ref "JP8") (pin "5") (pinfunction "5_5") (pintype "passive"))
    )
    (net (code "70") (name "N$15") (class "Default")
      (node (ref "JP3") (pin "1") (pinfunction "1_1") (pintype "passive"))
    )
    (net (code "71") (name "N$16") (class "Default")
      (node (ref "JP3") (pin "2") (pinfunction "2_2") (pintype "passive"))
    )
    (net (code "72") (name "NAS-CA") (class "Default")
      (node (ref "RASPBERRYPI") (pin "8") (pinfunction "8_8") (pintype "passive"))
      (node (ref "U5") (pin "5") (pinfunction "IN3_5") (pintype "bidirectional"))
    )
    (net (code "73") (name "NAS1ARX") (class "Default")
      (node (ref "IC2") (pin "13") (pinfunction "PH1(TXD2)_13") (pintype "bidirectional"))
      (node (ref "LED4") (pin "C") (pinfunction "C_C") (pintype "passive"))
      (node (ref "NAS") (pin "3") (pinfunction "3_3") (pintype "passive"))
      (node (ref "U16") (pin "1") (pinfunction "B0_1") (pintype "bidirectional"))
    )
    (net (code "74") (name "NAS1ATX") (class "Default")
      (node (ref "IC2") (pin "12") (pinfunction "PH0(RXD2)_12") (pintype "bidirectional"))
      (node (ref "LED3") (pin "C") (pinfunction "C_C") (pintype "passive"))
      (node (ref "NAS") (pin "2") (pinfunction "2_2") (pintype "passive"))
      (node (ref "U16") (pin "12") (pinfunction "A0_12") (pintype "bidirectional"))
    )
    (net (code "75") (name "NAS2LRX") (class "Default")
      (node (ref "LANNAS") (pin "2") (pinfunction "2_2") (pintype "passive"))
      (node (ref "U1") (pin "21") (pinfunction "TX2_21") (pintype "bidirectional"))
      (node (ref "U16") (pin "5") (pinfunction "B1_5") (pintype "bidirectional"))
    )
    (net (code "76") (name "NAS2LTX") (class "Default")
      (node (ref "LANNAS") (pin "3") (pinfunction "3_3") (pintype "passive"))
      (node (ref "U1") (pin "25") (pinfunction "RX2_25") (pintype "bidirectional"))
      (node (ref "U16") (pin "14") (pinfunction "A1_14") (pintype "bidirectional"))
    )
    (net (code "77") (name "NASPWR") (class "Default")
      (node (ref "Q10") (pin "3") (pinfunction "S_3") (pintype "passive"))
      (node (ref "RASPBERRYPI") (pin "13") (pinfunction "13_13") (pintype "passive"))
      (node (ref "U10") (pin "3") (pinfunction "SOURCE_3") (pintype "bidirectional"))
    )
    (net (code "78") (name "NASRX") (class "Default")
      (node (ref "NAS3V") (pin "2") (pinfunction "2_2") (pintype "passive"))
      (node (ref "Q14") (pin "2") (pinfunction "S_2") (pintype "passive"))
      (node (ref "R24") (pin "1") (pinfunction "1_1") (pintype "passive"))
      (node (ref "RASPBERRYPI") (pin "9") (pinfunction "9_9") (pintype "passive"))
    )
    (net (code "79") (name "NASRX5V") (class "Default")
      (node (ref "Q14") (pin "3") (pinfunction "D_3") (pintype "passive"))
      (node (ref "R27") (pin "1") (pinfunction "1_1") (pintype "passive"))
      (node (ref "U16") (pin "3") (pinfunction "B_3") (pintype "bidirectional"))
    )
    (net (code "80") (name "NASSCL") (class "Default")
      (node (ref "JP9") (pin "2") (pinfunction "2_2") (pintype "passive"))
      (node (ref "U11") (pin "10") (pinfunction "SCL_10") (pintype "bidirectional"))
      (node (ref "U13") (pin "10") (pinfunction "SCL_10") (pintype "bidirectional"))
    )
    (net (code "81") (name "NASSDA") (class "Default")
      (node (ref "JP9") (pin "3") (pinfunction "3_3") (pintype "passive"))
      (node (ref "U11") (pin "9") (pinfunction "SDA_9") (pintype "bidirectional"))
      (node (ref "U13") (pin "9") (pinfunction "SDA_9") (pintype "bidirectional"))
    )
    (net (code "82") (name "NASTX") (class "Default")
      (node (ref "NAS3V") (pin "3") (pinfunction "3_3") (pintype "passive"))
      (node (ref "Q13") (pin "2") (pinfunction "S_2") (pintype "passive"))
      (node (ref "R22") (pin "1") (pinfunction "1_1") (pintype "passive"))
      (node (ref "RASPBERRYPI") (pin "10") (pinfunction "10_10") (pintype "passive"))
    )
    (net (code "83") (name "NASTX5V") (class "Default")
      (node (ref "Q13") (pin "3") (pinfunction "D_3") (pintype "passive"))
      (node (ref "R23") (pin "1") (pinfunction "1_1") (pintype "passive"))
      (node (ref "U16") (pin "13") (pinfunction "A_13") (pintype "bidirectional"))
    )
    (net (code "84") (name "NAS_PWR") (class "Default")
      (node (ref "U10") (pin "2") (pinfunction "INPUT_2") (pintype "bidirectional"))
      (node (ref "U6") (pin "12") (pinfunction "OUT3_12") (pintype "bidirectional"))
    )
    (net (code "85") (name "Net-(3.3V\\-PadA)") (class "Default")
      (node (ref "3.3V\\") (pin "A") (pinfunction "A_A") (pintype "passive"))
      (node (ref "R11") (pin "2") (pinfunction "2_2") (pintype "passive"))
    )
    (net (code "86") (name "Net-(5V\\-PadA)") (class "Default")
      (node (ref "5V\\") (pin "A") (pinfunction "A_A") (pintype "passive"))
      (node (ref "R10") (pin "2") (pinfunction "2_2") (pintype "passive"))
    )
    (net (code "87") (name "Net-(9V\\-PadA)") (class "Default")
      (node (ref "9V\\") (pin "A") (pinfunction "A_A") (pintype "passive"))
      (node (ref "R12") (pin "2") (pinfunction "2_2") (pintype "passive"))
    )
    (net (code "88") (name "Net-(12V\\-PadA)") (class "Default")
      (node (ref "12V\\") (pin "A") (pinfunction "A_A") (pintype "passive"))
      (node (ref "R21") (pin "2") (pinfunction "2_2") (pintype "passive"))
    )
    (net (code "89") (name "Net-(13-PadA)") (class "Default")
      (node (ref "13") (pin "A") (pinfunction "A_A") (pintype "passive"))
      (node (ref "R25") (pin "2") (pinfunction "2_2") (pintype "passive"))
    )
    (net (code "90") (name "Net-(C9-Pad2)") (class "Default")
      (node (ref "C9") (pin "2") (pinfunction "2_2") (pintype "passive"))
      (node (ref "R8") (pin "2") (pinfunction "2_2") (pintype "passive"))
      (node (ref "R9") (pin "2") (pinfunction "2_2") (pintype "passive"))
      (node (ref "X1") (pin "10") (pinfunction "10_10") (pintype "bidirectional"))
      (node (ref "X1") (pin "15") (pinfunction "15_15") (pintype "bidirectional"))
    )
    (net (code "91") (name "Net-(CG-PadC)") (class "Default")
      (node (ref "CG") (pin "C") (pinfunction "C_C") (pintype "passive"))
      (node (ref "R16") (pin "1") (pinfunction "1_1") (pintype "passive"))
    )
    (net (code "92") (name "Net-(CHG-S)") (class "Default")
      (node (ref "CHG") (pin "3") (pinfunction "S_3") (pintype "passive"))
      (node (ref "T2") (pin "3") (pinfunction "1_3") (pintype "passive"))
    )
    (net (code "93") (name "Net-(EACT-PadA)") (class "Default")
      (node (ref "EACT") (pin "A") (pinfunction "A_A") (pintype "passive"))
      (node (ref "R6") (pin "2") (pinfunction "2_2") (pintype "passive"))
    )
    (net (code "94") (name "Net-(ELINK-PadA)") (class "Default")
      (node (ref "ELINK") (pin "A") (pinfunction "A_A") (pintype "passive"))
      (node (ref "R7") (pin "2") (pinfunction "2_2") (pintype "passive"))
    )
    (net (code "95") (name "Net-(ETHERNET-Pad1)") (class "Default")
      (node (ref "ETHERNET") (pin "1") (pinfunction "1_1") (pintype "passive"))
      (node (ref "X1") (pin "16") (pinfunction "16_16") (pintype "bidirectional"))
    )
    (net (code "96") (name "Net-(ETHERNET-Pad2)") (class "Default")
      (node (ref "ETHERNET") (pin "2") (pinfunction "2_2") (pintype "passive"))
      (node (ref "X1") (pin "14") (pinfunction "14_14") (pintype "bidirectional"))
    )
    (net (code "97") (name "Net-(ETHERNET-Pad3)") (class "Default")
      (node (ref "ETHERNET") (pin "3") (pinfunction "3_3") (pintype "passive"))
      (node (ref "ETHERNET") (pin "7") (pinfunction "7_7") (pintype "passive"))
      (node (ref "ETHERNET") (pin "8") (pinfunction "8_8") (pintype "passive"))
      (node (ref "R8") (pin "1") (pinfunction "1_1") (pintype "passive"))
      (node (ref "X1") (pin "11") (pinfunction "11_11") (pintype "bidirectional"))
    )
    (net (code "98") (name "Net-(ETHERNET-Pad4)") (class "Default")
      (node (ref "ETHERNET") (pin "4") (pinfunction "4_4") (pintype "passive"))
      (node (ref "ETHERNET") (pin "5") (pinfunction "5_5") (pintype "passive"))
      (node (ref "R9") (pin "1") (pinfunction "1_1") (pintype "passive"))
    )
    (net (code "99") (name "Net-(ETHERNET-Pad6)") (class "Default")
      (node (ref "ETHERNET") (pin "6") (pinfunction "6_6") (pintype "passive"))
      (node (ref "X1") (pin "9") (pinfunction "9_9") (pintype "bidirectional"))
    )
    (net (code "100") (name "Net-(F1-Pad2)") (class "Default")
      (node (ref "F1") (pin "2") (pinfunction "2_2") (pintype "passive"))
      (node (ref "J1") (pin "1") (pinfunction "1_1") (pintype "passive"))
    )
    (net (code "101") (name "Net-(F2-Pad2)") (class "Default")
      (node (ref "F2") (pin "2") (pinfunction "2_2") (pintype "passive"))
      (node (ref "J2") (pin "1") (pinfunction "1_1") (pintype "passive"))
    )
    (net (code "102") (name "Net-(F3-Pad2)") (class "Default")
      (node (ref "F3") (pin "2") (pinfunction "2_2") (pintype "passive"))
      (node (ref "J3") (pin "1") (pinfunction "1_1") (pintype "passive"))
    )
    (net (code "103") (name "Net-(IC1-3V3OUT)") (class "Default")
      (node (ref "C6") (pin "1") (pinfunction "1_1") (pintype "passive"))
      (node (ref "IC1") (pin "17") (pinfunction "3V3OUT_17") (pintype "output"))
      (node (ref "IC1") (pin "4") (pinfunction "VCCIO_4") (pintype "power_in"))
    )
    (net (code "104") (name "Net-(IC1-CBUS0)") (class "Default")
      (node (ref "IC1") (pin "23") (pinfunction "CBUS0_23") (pintype "bidirectional"))
      (node (ref "TX") (pin "C") (pinfunction "C_C") (pintype "passive"))
    )
    (net (code "105") (name "Net-(IC1-CBUS1)") (class "Default")
      (node (ref "IC1") (pin "22") (pinfunction "CBUS1_22") (pintype "bidirectional"))
      (node (ref "RX") (pin "C") (pinfunction "C_C") (pintype "passive"))
    )
    (net (code "106") (name "Net-(IC1-RXD)") (class "Default")
      (node (ref "IC1") (pin "5") (pinfunction "RXD_5") (pintype "input"))
      (node (ref "JP1") (pin "2") (pinfunction "2_2") (pintype "passive"))
    )
    (net (code "107") (name "Net-(IC1-TXD)") (class "Default")
      (node (ref "IC1") (pin "1") (pinfunction "TXD_1") (pintype "output"))
      (node (ref "JP1") (pin "1") (pinfunction "1_1") (pintype "passive"))
    )
    (net (code "108") (name "Net-(IC1-USBDM)") (class "Default")
      (node (ref "CN1") (pin "D-") (pinfunction "D-_D-") (pintype "bidirectional"))
      (node (ref "IC1") (pin "16") (pinfunction "USBDM_16") (pintype "bidirectional"))
      (node (ref "JP10") (pin "3") (pinfunction "3_3") (pintype "passive"))
    )
    (net (code "109") (name "Net-(IC1-USBDP)") (class "Default")
      (node (ref "CN1") (pin "D+") (pinfunction "D+_D+") (pintype "bidirectional"))
      (node (ref "IC1") (pin "15") (pinfunction "USBDP_15") (pintype "bidirectional"))
      (node (ref "JP10") (pin "2") (pinfunction "2_2") (pintype "passive"))
    )
    (net (code "110") (name "Net-(IC2-XTAL1)") (class "Default")
      (node (ref "IC2") (pin "34") (pinfunction "XTAL1_34") (pintype "input"))
      (node (ref "OSS") (pin "3") (pinfunction "OUT_3") (pintype "bidirectional"))
    )
    (net (code "111") (name "Net-(IC2-XTAL2)") (class "Default")
      (node (ref "IC2") (pin "33") (pinfunction "XTAL2_33") (pintype "output"))
      (node (ref "OSS") (pin "1") (pinfunction "IN_1") (pintype "bidirectional"))
    )
    (net (code "112") (name "Net-(IC3-RXD)") (class "Default")
      (node (ref "IC3") (pin "5") (pinfunction "RXD_5") (pintype "input"))
      (node (ref "U8") (pin "3") (pinfunction "R-1_3") (pintype "bidirectional"))
    )
    (net (code "113") (name "Net-(IC3-TXD)") (class "Default")
      (node (ref "IC3") (pin "1") (pinfunction "TXD_1") (pintype "output"))
      (node (ref "U8") (pin "15") (pinfunction "D-1_15") (pintype "bidirectional"))
    )
    (net (code "114") (name "Net-(IC3-USBDM)") (class "Default")
      (node (ref "IC3") (pin "16") (pinfunction "USBDM_16") (pintype "bidirectional"))
      (node (ref "JP13") (pin "2") (pinfunction "2_2") (pintype "passive"))
    )
    (net (code "115") (name "Net-(IC3-USBDP)") (class "Default")
      (node (ref "IC3") (pin "15") (pinfunction "USBDP_15") (pintype "bidirectional"))
      (node (ref "JP13") (pin "3") (pinfunction "3_3") (pintype "passive"))
    )
    (net (code "116") (name "Net-(IC3-VCC)") (class "Default")
      (node (ref "IC3") (pin "20") (pinfunction "VCC_20") (pintype "power_in"))
      (node (ref "IC3") (pin "4") (pinfunction "VCCIO_4") (pintype "power_in"))
      (node (ref "JP13") (pin "4") (pinfunction "4_4") (pintype "passive"))
      (node (ref "U8") (pin "12") (pinfunction "DE2_12") (pintype "bidirectional"))
      (node (ref "U8") (pin "16") (pinfunction "VCC_16") (pintype "bidirectional"))
      (node (ref "U8") (pin "4") (pinfunction "DE1_4") (pintype "bidirectional"))
    )
    (net (code "117") (name "Net-(IC4-RXD)") (class "Default")
      (node (ref "IC4") (pin "5") (pinfunction "RXD_5") (pintype "input"))
      (node (ref "U8") (pin "5") (pinfunction "R-2_5") (pintype "bidirectional"))
    )
    (net (code "118") (name "Net-(IC4-TXD)") (class "Default")
      (node (ref "IC4") (pin "1") (pinfunction "TXD_1") (pintype "output"))
      (node (ref "U8") (pin "9") (pinfunction "D-2_9") (pintype "bidirectional"))
    )
    (net (code "119") (name "Net-(IC4-USBDM)") (class "Default")
      (node (ref "IC4") (pin "16") (pinfunction "USBDM_16") (pintype "bidirectional"))
      (node (ref "JP14") (pin "2") (pinfunction "2_2") (pintype "passive"))
    )
    (net (code "120") (name "Net-(IC4-USBDP)") (class "Default")
      (node (ref "IC4") (pin "15") (pinfunction "USBDP_15") (pintype "bidirectional"))
      (node (ref "JP14") (pin "3") (pinfunction "3_3") (pintype "passive"))
    )
    (net (code "121") (name "Net-(IC4-VCC)") (class "Default")
      (node (ref "IC4") (pin "20") (pinfunction "VCC_20") (pintype "power_in"))
      (node (ref "IC4") (pin "4") (pinfunction "VCCIO_4") (pintype "power_in"))
      (node (ref "JP14") (pin "4") (pinfunction "4_4") (pintype "passive"))
    )
    (net (code "122") (name "Net-(ISP1-MOSI)") (class "Default")
      (node (ref "ISP1") (pin "4") (pinfunction "MOSI_4") (pintype "output"))
      (node (ref "U3") (pin "15") (pinfunction "PB3(MOSI/OC2)_15") (pintype "bidirectional"))
    )
    (net (code "123") (name "Net-(ISP1-SCK)") (class "Default")
      (node (ref "ISP1") (pin "3") (pinfunction "SCK_3") (pintype "output"))
      (node (ref "R14") (pin "1") (pinfunction "1_1") (pintype "passive"))
      (node (ref "U3") (pin "17") (pinfunction "PB5(SCK)_17") (pintype "bidirectional"))
    )
    (net (code "124") (name "Net-(JP12-Pad1)") (class "Default")
      (node (ref "JP12") (pin "1") (pinfunction "1_1") (pintype "passive"))
      (node (ref "K1") (pin "5") (pinfunction "5_5") (pintype "passive"))
    )
    (net (code "125") (name "Net-(JP12-Pad2)") (class "Default")
      (node (ref "JP12") (pin "2") (pinfunction "2_2") (pintype "passive"))
      (node (ref "K1") (pin "3") (pinfunction "3_3") (pintype "passive"))
    )
    (net (code "126") (name "Net-(K1B-P)") (class "Default")
      (node (ref "JP6") (pin "2") (pinfunction "2_2") (pintype "passive"))
      (node (ref "K1") (pin "1") (pinfunction "P_1") (pintype "passive"))
    )
    (net (code "127") (name "Net-(LED1-PadA)") (class "Default")
      (node (ref "LED1") (pin "A") (pinfunction "A_A") (pintype "passive"))
      (node (ref "R14") (pin "2") (pinfunction "2_2") (pintype "passive"))
    )
    (net (code "128") (name "Net-(LED3-PadA)") (class "Default")
      (node (ref "LED3") (pin "A") (pinfunction "A_A") (pintype "passive"))
      (node (ref "R34") (pin "1") (pinfunction "1_1") (pintype "passive"))
    )
    (net (code "129") (name "Net-(LED4-PadA)") (class "Default")
      (node (ref "LED4") (pin "A") (pinfunction "A_A") (pintype "passive"))
      (node (ref "R35") (pin "1") (pinfunction "1_1") (pintype "passive"))
    )
    (net (code "130") (name "Net-(LED5-PadA)") (class "Default")
      (node (ref "LED5") (pin "A") (pinfunction "A_A") (pintype "passive"))
      (node (ref "R36") (pin "1") (pinfunction "1_1") (pintype "passive"))
    )
    (net (code "131") (name "Net-(LED6-PadA)") (class "Default")
      (node (ref "LED6") (pin "A") (pinfunction "A_A") (pintype "passive"))
      (node (ref "R37") (pin "1") (pinfunction "1_1") (pintype "passive"))
    )
    (net (code "132") (name "Net-(Q1-D)") (class "Default")
      (node (ref "J1") (pin "2") (pinfunction "2_2") (pintype "passive"))
      (node (ref "Q1") (pin "4") (pinfunction "D_4") (pintype "passive"))
    )
    (net (code "133") (name "Net-(Q2-D)") (class "Default")
      (node (ref "J1") (pin "3") (pinfunction "3_3") (pintype "passive"))
      (node (ref "Q2") (pin "4") (pinfunction "D_4") (pintype "passive"))
    )
    (net (code "134") (name "Net-(Q3-D)") (class "Default")
      (node (ref "J1") (pin "4") (pinfunction "4_4") (pintype "passive"))
      (node (ref "Q3") (pin "4") (pinfunction "D_4") (pintype "passive"))
    )
    (net (code "135") (name "Net-(Q4-D)") (class "Default")
      (node (ref "J2") (pin "2") (pinfunction "2_2") (pintype "passive"))
      (node (ref "Q4") (pin "4") (pinfunction "D_4") (pintype "passive"))
    )
    (net (code "136") (name "Net-(Q5-D)") (class "Default")
      (node (ref "J2") (pin "3") (pinfunction "3_3") (pintype "passive"))
      (node (ref "Q5") (pin "4") (pinfunction "D_4") (pintype "passive"))
    )
    (net (code "137") (name "Net-(Q6-D)") (class "Default")
      (node (ref "J2") (pin "4") (pinfunction "4_4") (pintype "passive"))
      (node (ref "Q6") (pin "4") (pinfunction "D_4") (pintype "passive"))
    )
    (net (code "138") (name "Net-(Q7-D)") (class "Default")
      (node (ref "J3") (pin "2") (pinfunction "2_2") (pintype "passive"))
      (node (ref "Q7") (pin "4") (pinfunction "D_4") (pintype "passive"))
    )
    (net (code "139") (name "Net-(Q8-D)") (class "Default")
      (node (ref "J3") (pin "3") (pinfunction "3_3") (pintype "passive"))
      (node (ref "Q8") (pin "4") (pinfunction "D_4") (pintype "passive"))
    )
    (net (code "140") (name "Net-(Q9-D)") (class "Default")
      (node (ref "J3") (pin "4") (pinfunction "4_4") (pintype "passive"))
      (node (ref "Q9") (pin "4") (pinfunction "D_4") (pintype "passive"))
    )
    (net (code "141") (name "Net-(Q10-G)") (class "Default")
      (node (ref "Q10") (pin "1") (pinfunction "G_1") (pintype "passive"))
      (node (ref "U10") (pin "5") (pinfunction "GATE_5") (pintype "bidirectional"))
    )
    (net (code "142") (name "Net-(Q16-G)") (class "Default")
      (node (ref "Q16") (pin "1") (pinfunction "G_1") (pintype "passive"))
      (node (ref "U15") (pin "5") (pinfunction "GATE_5") (pintype "bidirectional"))
    )
    (net (code "143") (name "Net-(R3-Pad2)") (class "Default")
      (node (ref "R3") (pin "2") (pinfunction "2_2") (pintype "passive"))
      (node (ref "RX") (pin "A") (pinfunction "A_A") (pintype "passive"))
    )
    (net (code "144") (name "Net-(R4-Pad2)") (class "Default")
      (node (ref "R4") (pin "2") (pinfunction "2_2") (pintype "passive"))
      (node (ref "TX") (pin "A") (pinfunction "A_A") (pintype "passive"))
    )
    (net (code "145") (name "Net-(R5-Pad2)") (class "Default")
      (node (ref "R5") (pin "2") (pinfunction "2_2") (pintype "passive"))
      (node (ref "WIFI") (pin "A") (pinfunction "A_A") (pintype "passive"))
    )
    (net (code "146") (name "Net-(T2-4)") (class "Default")
      (node (ref "L2") (pin "2") (pinfunction "2_2") (pintype "passive"))
      (node (ref "T2") (pin "8") (pinfunction "4_8") (pintype "passive"))
    )
    (net (code "147") (name "Net-(U$16-A)") (class "Default")
      (node (ref "R45") (pin "1") (pinfunction "1_1") (pintype "passive"))
      (node (ref "U$16") (pin "1") (pinfunction "A_1") (pintype "bidirectional"))
    )
    (net (code "148") (name "Net-(U$17-A)") (class "Default")
      (node (ref "R47") (pin "1") (pinfunction "1_1") (pintype "passive"))
      (node (ref "U$17") (pin "1") (pinfunction "A_1") (pintype "bidirectional"))
    )
    (net (code "149") (name "Net-(U$18-A)") (class "Default")
      (node (ref "R44") (pin "1") (pinfunction "1_1") (pintype "passive"))
      (node (ref "U$18") (pin "1") (pinfunction "A_1") (pintype "bidirectional"))
    )
    (net (code "150") (name "Net-(U$19-A)") (class "Default")
      (node (ref "R46") (pin "1") (pinfunction "1_1") (pintype "passive"))
      (node (ref "U$19") (pin "1") (pinfunction "A_1") (pintype "bidirectional"))
    )
    (net (code "151") (name "Net-(U1-ELED2)") (class "Default")
      (node (ref "EACT") (pin "C") (pinfunction "C_C") (pintype "passive"))
      (node (ref "U1") (pin "20") (pinfunction "ELED2_20") (pintype "bidirectional"))
    )
    (net (code "152") (name "Net-(U1-RX+)") (class "Default")
      (node (ref "U1") (pin "14") (pinfunction "RX+_14") (pintype "bidirectional"))
      (node (ref "X1") (pin "6") (pinfunction "6_6") (pintype "bidirectional"))
    )
    (net (code "153") (name "Net-(U1-RX-)") (class "Default")
      (node (ref "U1") (pin "16") (pinfunction "RX-_16") (pintype "bidirectional"))
      (node (ref "X1") (pin "8") (pinfunction "8_8") (pintype "bidirectional"))
    )
    (net (code "154") (name "Net-(U1-RXCT)") (class "Default")
      (node (ref "U1") (pin "12") (pinfunction "RXCT_12") (pintype "bidirectional"))
      (node (ref "X1") (pin "7") (pinfunction "7_7") (pintype "bidirectional"))
    )
    (net (code "155") (name "Net-(U1-TX+)") (class "Default")
      (node (ref "U1") (pin "6") (pinfunction "TX+_6") (pintype "bidirectional"))
      (node (ref "X1") (pin "1") (pinfunction "1_1") (pintype "bidirectional"))
    )
    (net (code "156") (name "Net-(U1-TX-)") (class "Default")
      (node (ref "U1") (pin "8") (pinfunction "TX-_8") (pintype "bidirectional"))
      (node (ref "X1") (pin "3") (pinfunction "3_3") (pintype "bidirectional"))
    )
    (net (code "157") (name "Net-(U1-TXCT)") (class "Default")
      (node (ref "U1") (pin "10") (pinfunction "TXCT_10") (pintype "bidirectional"))
      (node (ref "X1") (pin "2") (pinfunction "2_2") (pintype "bidirectional"))
    )
    (net (code "158") (name "Net-(U3-PB0(ICP))") (class "Default")
      (node (ref "U3") (pin "12") (pinfunction "PB0(ICP)_12") (pintype "bidirectional"))
      (node (ref "U6") (pin "5") (pinfunction "IN3_5") (pintype "bidirectional"))
    )
    (net (code "159") (name "Net-(U3-PB1(OC1A))") (class "Default")
      (node (ref "U3") (pin "13") (pinfunction "PB1(OC1A)_13") (pintype "bidirectional"))
      (node (ref "U6") (pin "4") (pinfunction "IN2_4") (pintype "bidirectional"))
    )
    (net (code "160") (name "Net-(U3-PB2(SS{slash}OC1B))") (class "Default")
      (node (ref "U3") (pin "14") (pinfunction "PB2(SS/OC1B)_14") (pintype "bidirectional"))
      (node (ref "U6") (pin "3") (pinfunction "IN1_3") (pintype "bidirectional"))
    )
    (net (code "161") (name "Net-(U3-PB6(XTAL1{slash}TOSC1))") (class "Default")
      (node (ref "U3") (pin "7") (pinfunction "PB6(XTAL1/TOSC1)_7") (pintype "bidirectional"))
      (node (ref "X4") (pin "1") (pinfunction "IN_1") (pintype "bidirectional"))
    )
    (net (code "162") (name "Net-(U3-PB7(XTAL2{slash}TOSC2))") (class "Default")
      (node (ref "U3") (pin "8") (pinfunction "PB7(XTAL2/TOSC2)_8") (pintype "bidirectional"))
      (node (ref "X4") (pin "3") (pinfunction "OUT_3") (pintype "bidirectional"))
    )
    (net (code "163") (name "Net-(U3-PC0(ADC0))") (class "Default")
      (node (ref "R45") (pin "2") (pinfunction "2_2") (pintype "passive"))
      (node (ref "U3") (pin "23") (pinfunction "PC0(ADC0)_23") (pintype "bidirectional"))
    )
    (net (code "164") (name "Net-(U3-PC1(ADC1))") (class "Default")
      (node (ref "R46") (pin "2") (pinfunction "2_2") (pintype "passive"))
      (node (ref "U3") (pin "24") (pinfunction "PC1(ADC1)_24") (pintype "bidirectional"))
    )
    (net (code "165") (name "Net-(U3-PC2(ADC2))") (class "Default")
      (node (ref "R44") (pin "2") (pinfunction "2_2") (pintype "passive"))
      (node (ref "U3") (pin "25") (pinfunction "PC2(ADC2)_25") (pintype "bidirectional"))
    )
    (net (code "166") (name "Net-(U3-PC3(ADC3))") (class "Default")
      (node (ref "R47") (pin "2") (pinfunction "2_2") (pintype "passive"))
      (node (ref "U3") (pin "26") (pinfunction "PC3(ADC3)_26") (pintype "bidirectional"))
    )
    (net (code "167") (name "Net-(U3-PD3(INT1))") (class "Default")
      (node (ref "U3") (pin "1") (pinfunction "PD3(INT1)_1") (pintype "bidirectional"))
      (node (ref "U5") (pin "11") (pinfunction "OUT4_11") (pintype "bidirectional"))
    )
    (net (code "168") (name "Net-(U3-PD4(XCK{slash}T0))") (class "Default")
      (node (ref "U3") (pin "2") (pinfunction "PD4(XCK/T0)_2") (pintype "bidirectional"))
      (node (ref "U5") (pin "12") (pinfunction "OUT3_12") (pintype "bidirectional"))
    )
    (net (code "169") (name "Net-(U3-PD5(T1))") (class "Default")
      (node (ref "U3") (pin "9") (pinfunction "PD5(T1)_9") (pintype "bidirectional"))
      (node (ref "U5") (pin "13") (pinfunction "OUT2_13") (pintype "bidirectional"))
    )
    (net (code "170") (name "Net-(U3-PD6(AIN0))") (class "Default")
      (node (ref "U3") (pin "10") (pinfunction "PD6(AIN0)_10") (pintype "bidirectional"))
      (node (ref "U5") (pin "14") (pinfunction "OUT1_14") (pintype "bidirectional"))
    )
    (net (code "171") (name "Net-(U3-PD7(AIN1))") (class "Default")
      (node (ref "U3") (pin "11") (pinfunction "PD7(AIN1)_11") (pintype "bidirectional"))
      (node (ref "U6") (pin "6") (pinfunction "IN4_6") (pintype "bidirectional"))
    )
    (net (code "172") (name "Net-(U7-PROG)") (class "Default")
      (node (ref "R20") (pin "2") (pinfunction "2_2") (pintype "passive"))
      (node (ref "U7") (pin "5") (pinfunction "PROG_5") (pintype "input"))
    )
    (net (code "173") (name "Net-(U7-STAT)") (class "Default")
      (node (ref "R16") (pin "2") (pinfunction "2_2") (pintype "passive"))
      (node (ref "U7") (pin "1") (pinfunction "STAT_1") (pintype "output"))
    )
    (net (code "174") (name "Net-(U8-A-1)") (class "Default")
      (node (ref "JP15") (pin "3") (pinfunction "3_3") (pintype "passive"))
      (node (ref "U8") (pin "2") (pinfunction "A-1_2") (pintype "bidirectional"))
    )
    (net (code "175") (name "Net-(U8-A-2)") (class "Default")
      (node (ref "JP16") (pin "3") (pinfunction "3_3") (pintype "passive"))
      (node (ref "U8") (pin "6") (pinfunction "A-2_6") (pintype "bidirectional"))
    )
    (net (code "176") (name "Net-(U8-B-1)") (class "Default")
      (node (ref "JP15") (pin "4") (pinfunction "4_4") (pintype "passive"))
      (node (ref "U8") (pin "1") (pinfunction "B-1_1") (pintype "bidirectional"))
    )
    (net (code "177") (name "Net-(U8-B-2)") (class "Default")
      (node (ref "JP16") (pin "4") (pinfunction "4_4") (pintype "passive"))
      (node (ref "U8") (pin "7") (pinfunction "B-2_7") (pintype "bidirectional"))
    )
    (net (code "178") (name "Net-(U8-GND)") (class "Default")
      (node (ref "IC3") (pin "18") (pinfunction "GND_18") (pintype "power_in"))
      (node (ref "IC3") (pin "21") (pinfunction "GND_21") (pintype "power_in"))
      (node (ref "IC3") (pin "25") (pinfunction "GND_25") (pintype "power_in"))
      (node (ref "IC3") (pin "7") (pinfunction "GND_7") (pintype "power_in"))
      (node (ref "IC4") (pin "18") (pinfunction "GND_18") (pintype "power_in"))
      (node (ref "IC4") (pin "21") (pinfunction "GND_21") (pintype "power_in"))
      (node (ref "IC4") (pin "25") (pinfunction "GND_25") (pintype "power_in"))
      (node (ref "IC4") (pin "7") (pinfunction "GND_7") (pintype "power_in"))
      (node (ref "JP13") (pin "1") (pinfunction "1_1") (pintype "passive"))
      (node (ref "JP14") (pin "1") (pinfunction "1_1") (pintype "passive"))
      (node (ref "U8") (pin "8") (pinfunction "GND_8") (pintype "bidirectional"))
    )
    (net (code "179") (name "Net-(U8-Y-1)") (class "Default")
      (node (ref "JP15") (pin "1") (pinfunction "1_1") (pintype "passive"))
      (node (ref "U8") (pin "14") (pinfunction "Y-1_14") (pintype "bidirectional"))
    )
    (net (code "180") (name "Net-(U8-Y-2)") (class "Default")
      (node (ref "JP16") (pin "1") (pinfunction "1_1") (pintype "passive"))
      (node (ref "U8") (pin "10") (pinfunction "Y-2_10") (pintype "bidirectional"))
    )
    (net (code "181") (name "Net-(U8-Z-1)") (class "Default")
      (node (ref "JP15") (pin "2") (pinfunction "2_2") (pintype "passive"))
      (node (ref "U8") (pin "13") (pinfunction "Z-1_13") (pintype "bidirectional"))
    )
    (net (code "182") (name "Net-(U8-Z-2)") (class "Default")
      (node (ref "JP16") (pin "2") (pinfunction "2_2") (pintype "passive"))
      (node (ref "U8") (pin "11") (pinfunction "Z-2_11") (pintype "bidirectional"))
    )
    (net (code "183") (name "Net-(U9-CELL)") (class "Default")
      (node (ref "C22") (pin "1") (pinfunction "1_1") (pintype "passive"))
      (node (ref "R31") (pin "1") (pinfunction "1_1") (pintype "passive"))
      (node (ref "U9") (pin "2") (pinfunction "CELL_2") (pintype "bidirectional"))
    )
    (net (code "184") (name "Net-(U9-QST)") (class "Default")
      (node (ref "R32") (pin "2") (pinfunction "2_2") (pintype "passive"))
      (node (ref "U9") (pin "6") (pinfunction "QST_6") (pintype "bidirectional"))
    )
    (net (code "185") (name "Net-(U11-AIN0)") (class "Default")
      (node (ref "JP17") (pin "4") (pinfunction "4_4") (pintype "passive"))
      (node (ref "U11") (pin "4") (pinfunction "AIN0_4") (pintype "bidirectional"))
    )
    (net (code "186") (name "Net-(U11-AIN1)") (class "Default")
      (node (ref "JP17") (pin "3") (pinfunction "3_3") (pintype "passive"))
      (node (ref "U11") (pin "5") (pinfunction "AIN1_5") (pintype "bidirectional"))
    )
    (net (code "187") (name "Net-(U11-AIN2)") (class "Default")
      (node (ref "JP17") (pin "2") (pinfunction "2_2") (pintype "passive"))
      (node (ref "U11") (pin "6") (pinfunction "AIN2_6") (pintype "bidirectional"))
    )
    (net (code "188") (name "Net-(U11-AIN3)") (class "Default")
      (node (ref "JP17") (pin "1") (pinfunction "1_1") (pintype "passive"))
      (node (ref "U11") (pin "7") (pinfunction "AIN3_7") (pintype "bidirectional"))
    )
    (net (code "189") (name "Net-(U12-CPOUT)") (class "Default")
      (node (ref "C33") (pin "1") (pinfunction "1_1") (pintype "passive"))
      (node (ref "U12") (pin "20") (pinfunction "CPOUT_20") (pintype "bidirectional"))
    )
    (net (code "190") (name "Net-(U12-REGOUT)") (class "Default")
      (node (ref "C32") (pin "1") (pinfunction "1_1") (pintype "passive"))
      (node (ref "U12") (pin "10") (pinfunction "REGOUT_10") (pintype "bidirectional"))
    )
    (net (code "191") (name "Net-(U13-AIN0)") (class "Default")
      (node (ref "JP18") (pin "4") (pinfunction "4_4") (pintype "passive"))
      (node (ref "U13") (pin "4") (pinfunction "AIN0_4") (pintype "bidirectional"))
    )
    (net (code "192") (name "Net-(U13-AIN1)") (class "Default")
      (node (ref "JP18") (pin "3") (pinfunction "3_3") (pintype "passive"))
      (node (ref "U13") (pin "5") (pinfunction "AIN1_5") (pintype "bidirectional"))
    )
    (net (code "193") (name "Net-(U13-AIN2)") (class "Default")
      (node (ref "JP18") (pin "2") (pinfunction "2_2") (pintype "passive"))
      (node (ref "U13") (pin "6") (pinfunction "AIN2_6") (pintype "bidirectional"))
    )
    (net (code "194") (name "Net-(U13-AIN3)") (class "Default")
      (node (ref "JP18") (pin "1") (pinfunction "1_1") (pintype "passive"))
      (node (ref "U13") (pin "7") (pinfunction "AIN3_7") (pintype "bidirectional"))
    )
    (net (code "195") (name "Net-(U20-~{RST})") (class "Default")
      (node (ref "JP5") (pin "1") (pinfunction "1_1") (pintype "passive"))
      (node (ref "U20") (pin "1") (pinfunction "~{RST}_1") (pintype "bidirectional"))
    )
    (net (code "196") (name "O1") (class "Default")
      (node (ref "IC2") (pin "78") (pinfunction "(AD0)PA0_78") (pintype "bidirectional"))
      (node (ref "U47") (pin "12") (pinfunction "OUT8_12") (pintype "bidirectional"))
    )
    (net (code "197") (name "O2") (class "Default")
      (node (ref "IC2") (pin "77") (pinfunction "(AD1)PA1_77") (pintype "bidirectional"))
      (node (ref "U47") (pin "13") (pinfunction "OUT7_13") (pintype "bidirectional"))
    )
    (net (code "198") (name "O3") (class "Default")
      (node (ref "IC2") (pin "76") (pinfunction "(AD2)PA2_76") (pintype "bidirectional"))
      (node (ref "U47") (pin "14") (pinfunction "OUT6_14") (pintype "bidirectional"))
    )
    (net (code "199") (name "O4") (class "Default")
      (node (ref "IC2") (pin "75") (pinfunction "(AD3)PA3_75") (pintype "bidirectional"))
      (node (ref "U47") (pin "15") (pinfunction "OUT5_15") (pintype "bidirectional"))
    )
    (net (code "200") (name "O5") (class "Default")
      (node (ref "IC2") (pin "74") (pinfunction "(AD4)PA4_74") (pintype "bidirectional"))
      (node (ref "U47") (pin "16") (pinfunction "OUT4_16") (pintype "bidirectional"))
    )
    (net (code "201") (name "O6") (class "Default")
      (node (ref "IC2") (pin "73") (pinfunction "(AD5)PA5_73") (pintype "bidirectional"))
      (node (ref "U47") (pin "17") (pinfunction "OUT3_17") (pintype "bidirectional"))
    )
    (net (code "202") (name "O7") (class "Default")
      (node (ref "IC2") (pin "72") (pinfunction "(AD6)PA6_72") (pintype "bidirectional"))
      (node (ref "U47") (pin "18") (pinfunction "OUT2_18") (pintype "bidirectional"))
    )
    (net (code "203") (name "O8") (class "Default")
      (node (ref "IC2") (pin "71") (pinfunction "(AD7)PA7_71") (pintype "bidirectional"))
      (node (ref "U47") (pin "19") (pinfunction "OUT1_19") (pintype "bidirectional"))
    )
    (net (code "204") (name "O9") (class "Default")
      (node (ref "IC2") (pin "53") (pinfunction "(A8)PC0_53") (pintype "bidirectional"))
      (node (ref "U49") (pin "19") (pinfunction "OUT1_19") (pintype "bidirectional"))
    )
    (net (code "205") (name "O10") (class "Default")
      (node (ref "IC2") (pin "54") (pinfunction "(A9)PC1_54") (pintype "bidirectional"))
      (node (ref "U49") (pin "18") (pinfunction "OUT2_18") (pintype "bidirectional"))
    )
    (net (code "206") (name "O11") (class "Default")
      (node (ref "IC2") (pin "55") (pinfunction "(A10)PC2_55") (pintype "bidirectional"))
      (node (ref "U49") (pin "17") (pinfunction "OUT3_17") (pintype "bidirectional"))
    )
    (net (code "207") (name "O12") (class "Default")
      (node (ref "IC2") (pin "56") (pinfunction "(A11)PC3_56") (pintype "bidirectional"))
      (node (ref "U49") (pin "16") (pinfunction "OUT4_16") (pintype "bidirectional"))
    )
    (net (code "208") (name "O13") (class "Default")
      (node (ref "IC2") (pin "57") (pinfunction "(A12)PC4_57") (pintype "bidirectional"))
      (node (ref "U49") (pin "15") (pinfunction "OUT5_15") (pintype "bidirectional"))
    )
    (net (code "209") (name "O14") (class "Default")
      (node (ref "IC2") (pin "58") (pinfunction "(A13)PC5_58") (pintype "bidirectional"))
      (node (ref "U49") (pin "14") (pinfunction "OUT6_14") (pintype "bidirectional"))
    )
    (net (code "210") (name "O15") (class "Default")
      (node (ref "IC2") (pin "59") (pinfunction "(A14)PC6_59") (pintype "bidirectional"))
      (node (ref "U49") (pin "13") (pinfunction "OUT7_13") (pintype "bidirectional"))
    )
    (net (code "211") (name "O16") (class "Default")
      (node (ref "IC2") (pin "60") (pinfunction "(A15)PC7_60") (pintype "bidirectional"))
      (node (ref "U49") (pin "12") (pinfunction "OUT8_12") (pintype "bidirectional"))
    )
    (net (code "212") (name "PN13") (class "Default")
      (node (ref "IC2") (pin "26") (pinfunction "(OC0A/OC1C/PCINT7)PB7_26") (pintype "bidirectional"))
      (node (ref "R25") (pin "1") (pinfunction "1_1") (pintype "passive"))
      (node (ref "U5") (pin "3") (pinfunction "IN1_3") (pintype "bidirectional"))
    )
    (net (code "213") (name "RXD0") (class "Default")
      (node (ref "IC2") (pin "3") (pinfunction "(TXD0)PE1_3") (pintype "bidirectional"))
      (node (ref "USB") (pin "1") (pinfunction "1_1") (pintype "passive"))
    )
    (net (code "214") (name "RXD1") (class "Default")
      (node (ref "IC2") (pin "45") (pinfunction "(RXD1/INT2)PD2_45") (pintype "bidirectional"))
      (node (ref "LED5") (pin "C") (pinfunction "C_C") (pintype "passive"))
      (node (ref "U1") (pin "5") (pinfunction "TX1_5") (pintype "bidirectional"))
    )
    (net (code "215") (name "SCK-1") (class "Default")
      (node (ref "IC2") (pin "20") (pinfunction "(SCK/PCINT1)PB1_20") (pintype "bidirectional"))
      (node (ref "ICSP") (pin "3") (pinfunction "3_3") (pintype "passive"))
    )
    (net (code "216") (name "SCL") (class "Default")
      (node (ref "IC2") (pin "43") (pinfunction "(SCL/INT0)PD0_43") (pintype "bidirectional"))
      (node (ref "Q11") (pin "3") (pinfunction "D_3") (pintype "passive"))
      (node (ref "R38") (pin "1") (pinfunction "1_1") (pintype "passive"))
      (node (ref "R40") (pin "2") (pinfunction "2_2") (pintype "passive"))
      (node (ref "U2") (pin "26") (pinfunction "SCL_26") (pintype "bidirectional"))
    )
    (net (code "217") (name "SDA") (class "Default")
      (node (ref "IC2") (pin "44") (pinfunction "(SDA/INT1)PD1_44") (pintype "bidirectional"))
      (node (ref "Q12") (pin "3") (pinfunction "D_3") (pintype "passive"))
      (node (ref "R41") (pin "2") (pinfunction "2_2") (pintype "passive"))
      (node (ref "R42") (pin "1") (pinfunction "1_1") (pintype "passive"))
      (node (ref "U2") (pin "27") (pinfunction "SDA_27") (pintype "bidirectional"))
    )
    (net (code "218") (name "TXD0") (class "Default")
      (node (ref "IC2") (pin "2") (pinfunction "(RXD0/PCIN8)PE0_2") (pintype "bidirectional"))
      (node (ref "USB") (pin "2") (pinfunction "2_2") (pintype "passive"))
    )
    (net (code "219") (name "TXD1") (class "Default")
      (node (ref "IC2") (pin "46") (pinfunction "(TXD1/INT3)PD3_46") (pintype "bidirectional"))
      (node (ref "LED6") (pin "C") (pinfunction "C_C") (pintype "passive"))
      (node (ref "U1") (pin "9") (pinfunction "RX1_9") (pintype "bidirectional"))
    )
    (net (code "220") (name "USBPR") (class "Default")
      (node (ref "C10") (pin "A") (pinfunction "+_A") (pintype "passive"))
      (node (ref "C5") (pin "1") (pinfunction "1_1") (pintype "passive"))
      (node (ref "CN1") (pin "VBUS") (pinfunction "VBUS_VBUS") (pintype "power_in"))
      (node (ref "IC1") (pin "20") (pinfunction "VCC_20") (pintype "power_in"))
      (node (ref "JP10") (pin "4") (pinfunction "4_4") (pintype "passive"))
      (node (ref "R3") (pin "1") (pinfunction "1_1") (pintype "passive"))
      (node (ref "R4") (pin "1") (pinfunction "1_1") (pintype "passive"))
    )
    (net (code "221") (name "V+") (class "Default")
      (node (ref "C12") (pin "+") (pinfunction "+_+") (pintype "passive"))
      (node (ref "C13") (pin "+") (pinfunction "+_+") (pintype "passive"))
      (node (ref "C14") (pin "1") (pinfunction "1_1") (pintype "passive"))
      (node (ref "C15") (pin "1") (pinfunction "1_1") (pintype "passive"))
      (node (ref "C21") (pin "1") (pinfunction "1_1") (pintype "passive"))
      (node (ref "C23") (pin "+") (pinfunction "+_+") (pintype "passive"))
      (node (ref "ISP1") (pin "2") (pinfunction "VCC_2") (pintype "power_in"))
      (node (ref "R13") (pin "2") (pinfunction "2_2") (pintype "passive"))
      (node (ref "R15") (pin "2") (pinfunction "2_2") (pintype "passive"))
      (node (ref "R17") (pin "2") (pinfunction "2_2") (pintype "passive"))
      (node (ref "U20") (pin "5") (pinfunction "VCC_5") (pintype "bidirectional"))
      (node (ref "U3") (pin "18") (pinfunction "AVCC_18") (pintype "bidirectional"))
      (node (ref "U3") (pin "4") (pinfunction "VCC_4") (pintype "bidirectional"))
      (node (ref "U3") (pin "6") (pinfunction "VCC_6") (pintype "bidirectional"))
      (node (ref "U6") (pin "1") (pinfunction "VDD1_1") (pintype "bidirectional"))
      (node (ref "U9") (pin "3") (pinfunction "VDD_3") (pintype "bidirectional"))
      (node (ref "VREG") (pin "5") (pinfunction "OUT_5") (pintype "passive"))
    )
    (net (code "222") (name "VBATT") (class "Default")
      (node (ref "K1") (pin "7") (pinfunction "S_7") (pintype "passive"))
      (node (ref "R31") (pin "2") (pinfunction "2_2") (pintype "passive"))
      (node (ref "U7") (pin "3") (pinfunction "VBAT_3") (pintype "power_in"))
      (node (ref "VREG") (pin "1") (pinfunction "IN_1") (pintype "input"))
      (node (ref "VREG") (pin "3") (pinfunction "EN_3") (pintype "input"))
    )
    (net (code "223") (name "VBUS") (class "Default")
      (node (ref "C11") (pin "1") (pinfunction "1_1") (pintype "passive"))
      (node (ref "C25") (pin "1") (pinfunction "1_1") (pintype "passive"))
      (node (ref "CG") (pin "A") (pinfunction "A_A") (pintype "passive"))
      (node (ref "JP4") (pin "1") (pinfunction "1_1") (pintype "passive"))
      (node (ref "L2") (pin "1") (pinfunction "1_1") (pintype "passive"))
      (node (ref "U7") (pin "4") (pinfunction "VIN_4") (pintype "power_in"))
    )
    (net (code "224") (name "VIN") (class "Default")
      (node (ref "J4") (pin "1") (pinfunction "1_1") (pintype "passive"))
    )
    (net (code "225") (name "VIO") (class "Default")
      (node (ref "C35") (pin "1") (pinfunction "1_1") (pintype "passive"))
      (node (ref "SJ6") (pin "2") (pinfunction "2_2") (pintype "passive"))
      (node (ref "U12") (pin "8") (pinfunction "VLOGIC_8") (pintype "bidirectional"))
    )
    (net (code "226") (name "VRST") (class "Default")
      (node (ref "ISP1") (pin "5") (pinfunction "RST_5") (pintype "output"))
      (node (ref "JP5") (pin "2") (pinfunction "2_2") (pintype "passive"))
      (node (ref "R13") (pin "1") (pinfunction "1_1") (pintype "passive"))
      (node (ref "S3") (pin "3") (pinfunction "3_3") (pintype "passive"))
      (node (ref "S3") (pin "4") (pinfunction "4_4") (pintype "passive"))
      (node (ref "U3") (pin "29") (pinfunction "PC6(/RESET)_29") (pintype "bidirectional"))
    )
    (net (code "227") (name "WDKICK") (class "Default")
      (node (ref "ISP1") (pin "1") (pinfunction "MISO_1") (pintype "input"))
      (node (ref "U20") (pin "4") (pinfunction "WDI_4") (pintype "bidirectional"))
      (node (ref "U3") (pin "16") (pinfunction "PB4(MISO)_16") (pintype "bidirectional"))
    )
    (net (code "228") (name "WDSCL") (class "Default")
      (node (ref "R17") (pin "1") (pinfunction "1_1") (pintype "passive"))
      (node (ref "U3") (pin "28") (pinfunction "PC5(ADC5/SCL)_28") (pintype "bidirectional"))
      (node (ref "U9") (pin "7") (pinfunction "SCL_7") (pintype "bidirectional"))
    )
    (net (code "229") (name "WDSDA") (class "Default")
      (node (ref "R15") (pin "1") (pinfunction "1_1") (pintype "passive"))
      (node (ref "U3") (pin "27") (pinfunction "PC4(ADC4/SDA)_27") (pintype "bidirectional"))
      (node (ref "U9") (pin "8") (pinfunction "SDA_8") (pintype "bidirectional"))
    )
    (net (code "230") (name "WIFICONECT") (class "Default")
      (node (ref "U1") (pin "22") (pinfunction "WLANLED_22") (pintype "bidirectional"))
      (node (ref "WIFI") (pin "C") (pinfunction "C_C") (pintype "passive"))
    )
    (net (code "231") (name "\\") (class "Default")
      (node (ref "Q15") (pin "4") (pinfunction "G_4") (pintype "bidirectional"))
      (node (ref "R1") (pin "2") (pinfunction "2_2") (pintype "passive"))
      (node (ref "U6") (pin "11") (pinfunction "OUT4_11") (pintype "bidirectional"))
    )
    (net (code "232") (name "unconnected-(CHG-O-Pad1)") (class "Default")
      (node (ref "CHG") (pin "1") (pinfunction "O_1") (pintype "passive"))
    )
    (net (code "233") (name "unconnected-(CN1-PadID)") (class "Default")
      (node (ref "CN1") (pin "ID") (pinfunction "ID_ID") (pintype "bidirectional"))
    )
    (net (code "234") (name "unconnected-(IC1-CBUS2-Pad13)") (class "Default")
      (node (ref "IC1") (pin "13") (pinfunction "CBUS2_13") (pintype "bidirectional"))
    )
    (net (code "235") (name "unconnected-(IC1-CBUS3-Pad14)") (class "Default")
      (node (ref "IC1") (pin "14") (pinfunction "CBUS3_14") (pintype "bidirectional"))
    )
    (net (code "236") (name "unconnected-(IC1-CBUS4-Pad12)") (class "Default")
      (node (ref "IC1") (pin "12") (pinfunction "CBUS4_12") (pintype "bidirectional"))
    )
    (net (code "237") (name "unconnected-(IC1-OSCI-Pad27)") (class "Default")
      (node (ref "IC1") (pin "27") (pinfunction "OSCI_27") (pintype "input"))
    )
    (net (code "238") (name "unconnected-(IC1-OSCO-Pad28)") (class "Default")
      (node (ref "IC1") (pin "28") (pinfunction "OSCO_28") (pintype "output"))
    )
    (net (code "239") (name "unconnected-(IC1-~{CTS}-Pad11)") (class "Default")
      (node (ref "IC1") (pin "11") (pinfunction "~{CTS}_11") (pintype "input"))
    )
    (net (code "240") (name "unconnected-(IC1-~{DCD}-Pad10)") (class "Default")
      (node (ref "IC1") (pin "10") (pinfunction "~{DCD}_10") (pintype "input"))
    )
    (net (code "241") (name "unconnected-(IC1-~{DSR}-Pad9)") (class "Default")
      (node (ref "IC1") (pin "9") (pinfunction "~{DSR}_9") (pintype "input"))
    )
    (net (code "242") (name "unconnected-(IC1-~{DTR}-Pad2)") (class "Default")
      (node (ref "IC1") (pin "2") (pinfunction "~{DTR}_2") (pintype "output"))
    )
    (net (code "243") (name "unconnected-(IC1-~{RESET}-Pad19)") (class "Default")
      (node (ref "IC1") (pin "19") (pinfunction "~{RESET}_19") (pintype "input"))
    )
    (net (code "244") (name "unconnected-(IC1-~{RI}-Pad6)") (class "Default")
      (node (ref "IC1") (pin "6") (pinfunction "~{RI}_6") (pintype "input"))
    )
    (net (code "245") (name "unconnected-(IC1-~{RTS}-Pad3)") (class "Default")
      (node (ref "IC1") (pin "3") (pinfunction "~{RTS}_3") (pintype "output"))
    )
    (net (code "246") (name "unconnected-(IC2-(ALE)PG2-Pad70)") (class "Default")
      (node (ref "IC2") (pin "70") (pinfunction "(ALE)PG2_70") (pintype "bidirectional"))
    )
    (net (code "247") (name "unconnected-(IC2-(CLKO{slash}ICP3{slash}INT7)PE7-Pad9)") (class "Default")
      (node (ref "IC2") (pin "9") (pinfunction "(CLKO/ICP3/INT7)PE7_9") (pintype "bidirectional"))
    )
    (net (code "248") (name "unconnected-(IC2-(ICP1)PD4-Pad47)") (class "Default")
      (node (ref "IC2") (pin "47") (pinfunction "(ICP1)PD4_47") (pintype "bidirectional"))
    )
    (net (code "249") (name "unconnected-(IC2-(OC0B)PG5-Pad1)") (class "Default")
      (node (ref "IC2") (pin "1") (pinfunction "(OC0B)PG5_1") (pintype "bidirectional"))
    )
    (net (code "250") (name "unconnected-(IC2-(OC1B{slash}PCINT6)PB6-Pad25)") (class "Default")
      (node (ref "IC2") (pin "25") (pinfunction "(OC1B/PCINT6)PB6_25") (pintype "bidirectional"))
    )
    (net (code "251") (name "unconnected-(IC2-(OC2A{slash}PCINT4)PB4-Pad23)") (class "Default")
      (node (ref "IC2") (pin "23") (pinfunction "(OC2A/PCINT4)PB4_23") (pintype "bidirectional"))
    )
    (net (code "252") (name "unconnected-(IC2-(OC3A{slash}AIN1)PE3-Pad5)") (class "Default")
      (node (ref "IC2") (pin "5") (pinfunction "(OC3A/AIN1)PE3_5") (pintype "bidirectional"))
    )
    (net (code "253") (name "unconnected-(IC2-(OC3B{slash}INT4)PE4-Pad6)") (class "Default")
      (node (ref "IC2") (pin "6") (pinfunction "(OC3B/INT4)PE4_6") (pintype "bidirectional"))
    )
    (net (code "254") (name "unconnected-(IC2-(OC3C{slash}INT5)PE5-Pad7)") (class "Default")
      (node (ref "IC2") (pin "7") (pinfunction "(OC3C/INT5)PE5_7") (pintype "bidirectional"))
    )
    (net (code "255") (name "unconnected-(IC2-(RD)PG1-Pad52)") (class "Default")
      (node (ref "IC2") (pin "52") (pinfunction "(RD)PG1_52") (pintype "bidirectional"))
    )
    (net (code "256") (name "unconnected-(IC2-(SS{slash}PCINT0)PB0-Pad19)") (class "Default")
      (node (ref "IC2") (pin "19") (pinfunction "(SS/PCINT0)PB0_19") (pintype "bidirectional"))
    )
    (net (code "257") (name "unconnected-(IC2-(T0)PD7-Pad50)") (class "Default")
      (node (ref "IC2") (pin "50") (pinfunction "(T0)PD7_50") (pintype "bidirectional"))
    )
    (net (code "258") (name "unconnected-(IC2-(T1)PD6-Pad49)") (class "Default")
      (node (ref "IC2") (pin "49") (pinfunction "(T1)PD6_49") (pintype "bidirectional"))
    )
    (net (code "259") (name "unconnected-(IC2-(T3{slash}INT6)PE6-Pad8)") (class "Default")
      (node (ref "IC2") (pin "8") (pinfunction "(T3/INT6)PE6_8") (pintype "bidirectional"))
    )
    (net (code "260") (name "unconnected-(IC2-(TOSC1)PG4-Pad29)") (class "Default")
      (node (ref "IC2") (pin "29") (pinfunction "(TOSC1)PG4_29") (pintype "bidirectional"))
    )
    (net (code "261") (name "unconnected-(IC2-(TOSC2)PG3-Pad28)") (class "Default")
      (node (ref "IC2") (pin "28") (pinfunction "(TOSC2)PG3_28") (pintype "bidirectional"))
    )
    (net (code "262") (name "unconnected-(IC2-(WR)PG0-Pad51)") (class "Default")
      (node (ref "IC2") (pin "51") (pinfunction "(WR)PG0_51") (pintype "bidirectional"))
    )
    (net (code "263") (name "unconnected-(IC2-(XCK0{slash}AIN0)PE2-Pad4)") (class "Default")
      (node (ref "IC2") (pin "4") (pinfunction "(XCK0/AIN0)PE2_4") (pintype "bidirectional"))
    )
    (net (code "264") (name "unconnected-(IC2-(XCK1)PD5-Pad48)") (class "Default")
      (node (ref "IC2") (pin "48") (pinfunction "(XCK1)PD5_48") (pintype "bidirectional"))
    )
    (net (code "265") (name "unconnected-(IC2-AREF-Pad98)") (class "Default")
      (node (ref "IC2") (pin "98") (pinfunction "AREF_98") (pintype "bidirectional"))
    )
    (net (code "266") (name "unconnected-(IC2-PH2(XCK2)-Pad14)") (class "Default")
      (node (ref "IC2") (pin "14") (pinfunction "PH2(XCK2)_14") (pintype "bidirectional"))
    )
    (net (code "267") (name "unconnected-(IC2-PH3(OC4A)-Pad15)") (class "Default")
      (node (ref "IC2") (pin "15") (pinfunction "PH3(OC4A)_15") (pintype "bidirectional"))
    )
    (net (code "268") (name "unconnected-(IC2-PH4(OC4B)-Pad16)") (class "Default")
      (node (ref "IC2") (pin "16") (pinfunction "PH4(OC4B)_16") (pintype "bidirectional"))
    )
    (net (code "269") (name "unconnected-(IC2-PH5(OC4C)-Pad17)") (class "Default")
      (node (ref "IC2") (pin "17") (pinfunction "PH5(OC4C)_17") (pintype "bidirectional"))
    )
    (net (code "270") (name "unconnected-(IC2-PH6(OC2B)-Pad18)") (class "Default")
      (node (ref "IC2") (pin "18") (pinfunction "PH6(OC2B)_18") (pintype "bidirectional"))
    )
    (net (code "271") (name "unconnected-(IC2-PH7(T4)-Pad27)") (class "Default")
      (node (ref "IC2") (pin "27") (pinfunction "PH7(T4)_27") (pintype "bidirectional"))
    )
    (net (code "272") (name "unconnected-(IC2-PJ2(XCK3{slash}PCINT11)-Pad65)") (class "Default")
      (node (ref "IC2") (pin "65") (pinfunction "PJ2(XCK3/PCINT11)_65") (pintype "bidirectional"))
    )
    (net (code "273") (name "unconnected-(IC2-PJ3(PCINT12)-Pad66)") (class "Default")
      (node (ref "IC2") (pin "66") (pinfunction "PJ3(PCINT12)_66") (pintype "bidirectional"))
    )
    (net (code "274") (name "unconnected-(IC2-PJ4(PCINT13)-Pad67)") (class "Default")
      (node (ref "IC2") (pin "67") (pinfunction "PJ4(PCINT13)_67") (pintype "bidirectional"))
    )
    (net (code "275") (name "unconnected-(IC2-PJ5(PCINT14)-Pad68)") (class "Default")
      (node (ref "IC2") (pin "68") (pinfunction "PJ5(PCINT14)_68") (pintype "bidirectional"))
    )
    (net (code "276") (name "unconnected-(IC2-PJ6(PCINT15)-Pad69)") (class "Default")
      (node (ref "IC2") (pin "69") (pinfunction "PJ6(PCINT15)_69") (pintype "bidirectional"))
    )
    (net (code "277") (name "unconnected-(IC2-PJ7-Pad79)") (class "Default")
      (node (ref "IC2") (pin "79") (pinfunction "PJ7_79") (pintype "bidirectional"))
    )
    (net (code "278") (name "unconnected-(IC2-PK2(ADC10{slash}PCINT18)-Pad87)") (class "Default")
      (node (ref "IC2") (pin "87") (pinfunction "PK2(ADC10/PCINT18)_87") (pintype "bidirectional"))
    )
    (net (code "279") (name "unconnected-(IC2-PK3(ADC11{slash}PCINT19)-Pad86)") (class "Default")
      (node (ref "IC2") (pin "86") (pinfunction "PK3(ADC11/PCINT19)_86") (pintype "bidirectional"))
    )
    (net (code "280") (name "unconnected-(IC2-PK4(ADC12{slash}PCINT20)-Pad85)") (class "Default")
      (node (ref "IC2") (pin "85") (pinfunction "PK4(ADC12/PCINT20)_85") (pintype "bidirectional"))
    )
    (net (code "281") (name "unconnected-(IC2-PK5(ADC13{slash}PCINT21)-Pad84)") (class "Default")
      (node (ref "IC2") (pin "84") (pinfunction "PK5(ADC13/PCINT21)_84") (pintype "bidirectional"))
    )
    (net (code "282") (name "unconnected-(IC2-PK6(ADC14{slash}PCINT22)-Pad83)") (class "Default")
      (node (ref "IC2") (pin "83") (pinfunction "PK6(ADC14/PCINT22)_83") (pintype "bidirectional"))
    )
    (net (code "283") (name "unconnected-(IC2-PK7(ADC15{slash}PCINT23)-Pad82)") (class "Default")
      (node (ref "IC2") (pin "82") (pinfunction "PK7(ADC15/PCINT23)_82") (pintype "bidirectional"))
    )
    (net (code "284") (name "unconnected-(IC2-PL0(ICP4)-Pad35)") (class "Default")
      (node (ref "IC2") (pin "35") (pinfunction "PL0(ICP4)_35") (pintype "bidirectional"))
    )
    (net (code "285") (name "unconnected-(IC2-PL1(ICP5)-Pad36)") (class "Default")
      (node (ref "IC2") (pin "36") (pinfunction "PL1(ICP5)_36") (pintype "bidirectional"))
    )
    (net (code "286") (name "unconnected-(IC2-PL2(T5)-Pad37)") (class "Default")
      (node (ref "IC2") (pin "37") (pinfunction "PL2(T5)_37") (pintype "bidirectional"))
    )
    (net (code "287") (name "unconnected-(IC2-PL3(OC5A)-Pad38)") (class "Default")
      (node (ref "IC2") (pin "38") (pinfunction "PL3(OC5A)_38") (pintype "bidirectional"))
    )
    (net (code "288") (name "unconnected-(IC2-PL4(OC5B)-Pad39)") (class "Default")
      (node (ref "IC2") (pin "39") (pinfunction "PL4(OC5B)_39") (pintype "bidirectional"))
    )
    (net (code "289") (name "unconnected-(IC2-PL5(OC5C)-Pad40)") (class "Default")
      (node (ref "IC2") (pin "40") (pinfunction "PL5(OC5C)_40") (pintype "bidirectional"))
    )
    (net (code "290") (name "unconnected-(IC2-PL6-Pad41)") (class "Default")
      (node (ref "IC2") (pin "41") (pinfunction "PL6_41") (pintype "bidirectional"))
    )
    (net (code "291") (name "unconnected-(IC2-PL7-Pad42)") (class "Default")
      (node (ref "IC2") (pin "42") (pinfunction "PL7_42") (pintype "bidirectional"))
    )
    (net (code "292") (name "unconnected-(IC3-3V3OUT-Pad17)") (class "Default")
      (node (ref "IC3") (pin "17") (pinfunction "3V3OUT_17") (pintype "output"))
    )
    (net (code "293") (name "unconnected-(IC3-CBUS0-Pad23)") (class "Default")
      (node (ref "IC3") (pin "23") (pinfunction "CBUS0_23") (pintype "bidirectional"))
    )
    (net (code "294") (name "unconnected-(IC3-CBUS1-Pad22)") (class "Default")
      (node (ref "IC3") (pin "22") (pinfunction "CBUS1_22") (pintype "bidirectional"))
    )
    (net (code "295") (name "unconnected-(IC3-CBUS2-Pad13)") (class "Default")
      (node (ref "IC3") (pin "13") (pinfunction "CBUS2_13") (pintype "bidirectional"))
    )
    (net (code "296") (name "unconnected-(IC3-CBUS3-Pad14)") (class "Default")
      (node (ref "IC3") (pin "14") (pinfunction "CBUS3_14") (pintype "bidirectional"))
    )
    (net (code "297") (name "unconnected-(IC3-CBUS4-Pad12)") (class "Default")
      (node (ref "IC3") (pin "12") (pinfunction "CBUS4_12") (pintype "bidirectional"))
    )
    (net (code "298") (name "unconnected-(IC3-OSCI-Pad27)") (class "Default")
      (node (ref "IC3") (pin "27") (pinfunction "OSCI_27") (pintype "input"))
    )
    (net (code "299") (name "unconnected-(IC3-OSCO-Pad28)") (class "Default")
      (node (ref "IC3") (pin "28") (pinfunction "OSCO_28") (pintype "output"))
    )
    (net (code "300") (name "unconnected-(IC3-TEST-Pad26)") (class "Default")
      (node (ref "IC3") (pin "26") (pinfunction "TEST_26") (pintype "input"))
    )
    (net (code "301") (name "unconnected-(IC3-~{CTS}-Pad11)") (class "Default")
      (node (ref "IC3") (pin "11") (pinfunction "~{CTS}_11") (pintype "input"))
    )
    (net (code "302") (name "unconnected-(IC3-~{DCD}-Pad10)") (class "Default")
      (node (ref "IC3") (pin "10") (pinfunction "~{DCD}_10") (pintype "input"))
    )
    (net (code "303") (name "unconnected-(IC3-~{DSR}-Pad9)") (class "Default")
      (node (ref "IC3") (pin "9") (pinfunction "~{DSR}_9") (pintype "input"))
    )
    (net (code "304") (name "unconnected-(IC3-~{DTR}-Pad2)") (class "Default")
      (node (ref "IC3") (pin "2") (pinfunction "~{DTR}_2") (pintype "output"))
    )
    (net (code "305") (name "unconnected-(IC3-~{RESET}-Pad19)") (class "Default")
      (node (ref "IC3") (pin "19") (pinfunction "~{RESET}_19") (pintype "input"))
    )
    (net (code "306") (name "unconnected-(IC3-~{RI}-Pad6)") (class "Default")
      (node (ref "IC3") (pin "6") (pinfunction "~{RI}_6") (pintype "input"))
    )
    (net (code "307") (name "unconnected-(IC3-~{RTS}-Pad3)") (class "Default")
      (node (ref "IC3") (pin "3") (pinfunction "~{RTS}_3") (pintype "output"))
    )
    (net (code "308") (name "unconnected-(IC4-3V3OUT-Pad17)") (class "Default")
      (node (ref "IC4") (pin "17") (pinfunction "3V3OUT_17") (pintype "output"))
    )
    (net (code "309") (name "unconnected-(IC4-CBUS0-Pad23)") (class "Default")
      (node (ref "IC4") (pin "23") (pinfunction "CBUS0_23") (pintype "bidirectional"))
    )
    (net (code "310") (name "unconnected-(IC4-CBUS1-Pad22)") (class "Default")
      (node (ref "IC4") (pin "22") (pinfunction "CBUS1_22") (pintype "bidirectional"))
    )
    (net (code "311") (name "unconnected-(IC4-CBUS2-Pad13)") (class "Default")
      (node (ref "IC4") (pin "13") (pinfunction "CBUS2_13") (pintype "bidirectional"))
    )
    (net (code "312") (name "unconnected-(IC4-CBUS3-Pad14)") (class "Default")
      (node (ref "IC4") (pin "14") (pinfunction "CBUS3_14") (pintype "bidirectional"))
    )
    (net (code "313") (name "unconnected-(IC4-CBUS4-Pad12)") (class "Default")
      (node (ref "IC4") (pin "12") (pinfunction "CBUS4_12") (pintype "bidirectional"))
    )
    (net (code "314") (name "unconnected-(IC4-OSCI-Pad27)") (class "Default")
      (node (ref "IC4") (pin "27") (pinfunction "OSCI_27") (pintype "input"))
    )
    (net (code "315") (name "unconnected-(IC4-OSCO-Pad28)") (class "Default")
      (node (ref "IC4") (pin "28") (pinfunction "OSCO_28") (pintype "output"))
    )
    (net (code "316") (name "unconnected-(IC4-TEST-Pad26)") (class "Default")
      (node (ref "IC4") (pin "26") (pinfunction "TEST_26") (pintype "input"))
    )
    (net (code "317") (name "unconnected-(IC4-~{CTS}-Pad11)") (class "Default")
      (node (ref "IC4") (pin "11") (pinfunction "~{CTS}_11") (pintype "input"))
    )
    (net (code "318") (name "unconnected-(IC4-~{DCD}-Pad10)") (class "Default")
      (node (ref "IC4") (pin "10") (pinfunction "~{DCD}_10") (pintype "input"))
    )
    (net (code "319") (name "unconnected-(IC4-~{DSR}-Pad9)") (class "Default")
      (node (ref "IC4") (pin "9") (pinfunction "~{DSR}_9") (pintype "input"))
    )
    (net (code "320") (name "unconnected-(IC4-~{DTR}-Pad2)") (class "Default")
      (node (ref "IC4") (pin "2") (pinfunction "~{DTR}_2") (pintype "output"))
    )
    (net (code "321") (name "unconnected-(IC4-~{RESET}-Pad19)") (class "Default")
      (node (ref "IC4") (pin "19") (pinfunction "~{RESET}_19") (pintype "input"))
    )
    (net (code "322") (name "unconnected-(IC4-~{RI}-Pad6)") (class "Default")
      (node (ref "IC4") (pin "6") (pinfunction "~{RI}_6") (pintype "input"))
    )
    (net (code "323") (name "unconnected-(IC4-~{RTS}-Pad3)") (class "Default")
      (node (ref "IC4") (pin "3") (pinfunction "~{RTS}_3") (pintype "output"))
    )
    (net (code "324") (name "unconnected-(J6-Pad1)") (class "Default")
      (node (ref "J6") (pin "1") (pinfunction "1_1") (pintype "passive"))
    )
    (net (code "325") (name "unconnected-(J6-Pad2)") (class "Default")
      (node (ref "J6") (pin "2") (pinfunction "2_2") (pintype "passive"))
    )
    (net (code "326") (name "unconnected-(J6-Pad3)") (class "Default")
      (node (ref "J6") (pin "3") (pinfunction "3_3") (pintype "passive"))
    )
    (net (code "327") (name "unconnected-(J6-Pad4)") (class "Default")
      (node (ref "J6") (pin "4") (pinfunction "4_4") (pintype "passive"))
    )
    (net (code "328") (name "unconnected-(J6-Pad5)") (class "Default")
      (node (ref "J6") (pin "5") (pinfunction "5_5") (pintype "passive"))
    )
    (net (code "329") (name "unconnected-(J8-Pad7)") (class "Default")
      (node (ref "J8") (pin "7") (pinfunction "7_7") (pintype "passive"))
    )
    (net (code "330") (name "unconnected-(JP9-Pad1)") (class "Default")
      (node (ref "JP9") (pin "1") (pinfunction "1_1") (pintype "passive"))
    )
    (net (code "331") (name "unconnected-(JP9-Pad4)") (class "Default")
      (node (ref "JP9") (pin "4") (pinfunction "4_4") (pintype "passive"))
    )
    (net (code "332") (name "unconnected-(JP9-Pad5)") (class "Default")
      (node (ref "JP9") (pin "5") (pinfunction "5_5") (pintype "passive"))
    )
    (net (code "333") (name "unconnected-(JP9-Pad8)") (class "Default")
      (node (ref "JP9") (pin "8") (pinfunction "8_8") (pintype "passive"))
    )
    (net (code "334") (name "unconnected-(JP9-Pad9)") (class "Default")
      (node (ref "JP9") (pin "9") (pinfunction "9_9") (pintype "passive"))
    )
    (net (code "335") (name "unconnected-(JP9-Pad10)") (class "Default")
      (node (ref "JP9") (pin "10") (pinfunction "10_10") (pintype "passive"))
    )
    (net (code "336") (name "unconnected-(JP9-Pad11)") (class "Default")
      (node (ref "JP9") (pin "11") (pinfunction "11_11") (pintype "passive"))
    )
    (net (code "337") (name "unconnected-(JP9-Pad12)") (class "Default")
      (node (ref "JP9") (pin "12") (pinfunction "12_12") (pintype "passive"))
    )
    (net (code "338") (name "unconnected-(JP9-Pad13)") (class "Default")
      (node (ref "JP9") (pin "13") (pinfunction "13_13") (pintype "passive"))
    )
    (net (code "339") (name "unconnected-(RASPBERRYPI-Pad1)") (class "Default")
      (node (ref "RASPBERRYPI") (pin "1") (pinfunction "1_1") (pintype "passive"))
    )
    (net (code "340") (name "unconnected-(RASPBERRYPI-Pad2)") (class "Default")
      (node (ref "RASPBERRYPI") (pin "2") (pinfunction "2_2") (pintype "passive"))
    )
    (net (code "341") (name "unconnected-(RASPBERRYPI-Pad3)") (class "Default")
      (node (ref "RASPBERRYPI") (pin "3") (pinfunction "3_3") (pintype "passive"))
    )
    (net (code "342") (name "unconnected-(RASPBERRYPI-Pad4)") (class "Default")
      (node (ref "RASPBERRYPI") (pin "4") (pinfunction "4_4") (pintype "passive"))
    )
    (net (code "343") (name "unconnected-(RASPBERRYPI-Pad5)") (class "Default")
      (node (ref "RASPBERRYPI") (pin "5") (pinfunction "5_5") (pintype "passive"))
    )
    (net (code "344") (name "unconnected-(RASPBERRYPI-Pad6)") (class "Default")
      (node (ref "RASPBERRYPI") (pin "6") (pinfunction "6_6") (pintype "passive"))
    )
    (net (code "345") (name "unconnected-(RASPBERRYPI-Pad7)") (class "Default")
      (node (ref "RASPBERRYPI") (pin "7") (pinfunction "7_7") (pintype "passive"))
    )
    (net (code "346") (name "unconnected-(RASPBERRYPI-Pad12)") (class "Default")
      (node (ref "RASPBERRYPI") (pin "12") (pinfunction "12_12") (pintype "passive"))
    )
    (net (code "347") (name "unconnected-(U1-CP3-Pad17)") (class "Default")
      (node (ref "U1") (pin "17") (pinfunction "CP3_17") (pintype "bidirectional"))
    )
    (net (code "348") (name "unconnected-(U1-CP4-Pad19)") (class "Default")
      (node (ref "U1") (pin "19") (pinfunction "CP4_19") (pintype "bidirectional"))
    )
    (net (code "349") (name "unconnected-(U1-CP5-Pad29)") (class "Default")
      (node (ref "U1") (pin "29") (pinfunction "CP5_29") (pintype "bidirectional"))
    )
    (net (code "350") (name "unconnected-(U1-CP6-Pad31)") (class "Default")
      (node (ref "U1") (pin "31") (pinfunction "CP6_31") (pintype "bidirectional"))
    )
    (net (code "351") (name "unconnected-(U1-CP7-Pad33)") (class "Default")
      (node (ref "U1") (pin "33") (pinfunction "CP7_33") (pintype "bidirectional"))
    )
    (net (code "352") (name "unconnected-(U1-CP8-Pad35)") (class "Default")
      (node (ref "U1") (pin "35") (pinfunction "CP8_35") (pintype "bidirectional"))
    )
    (net (code "353") (name "unconnected-(U1-CTS1-Pad11)") (class "Default")
      (node (ref "U1") (pin "11") (pinfunction "CTS1_11") (pintype "bidirectional"))
    )
    (net (code "354") (name "unconnected-(U1-CTS2-Pad27)") (class "Default")
      (node (ref "U1") (pin "27") (pinfunction "CTS2_27") (pintype "bidirectional"))
    )
    (net (code "355") (name "unconnected-(U1-RTS1-Pad7)") (class "Default")
      (node (ref "U1") (pin "7") (pinfunction "RTS1_7") (pintype "bidirectional"))
    )
    (net (code "356") (name "unconnected-(U1-RTS2-Pad23)") (class "Default")
      (node (ref "U1") (pin "23") (pinfunction "RTS2_23") (pintype "bidirectional"))
    )
    (net (code "357") (name "unconnected-(U2-PWM9-Pad16)") (class "Default")
      (node (ref "U2") (pin "16") (pinfunction "PWM9_16") (pintype "output"))
    )
    (net (code "358") (name "unconnected-(U2-PWM10-Pad17)") (class "Default")
      (node (ref "U2") (pin "17") (pinfunction "PWM10_17") (pintype "output"))
    )
    (net (code "359") (name "unconnected-(U2-PWM11-Pad18)") (class "Default")
      (node (ref "U2") (pin "18") (pinfunction "PWM11_18") (pintype "output"))
    )
    (net (code "360") (name "unconnected-(U2-PWM12-Pad19)") (class "Default")
      (node (ref "U2") (pin "19") (pinfunction "PWM12_19") (pintype "output"))
    )
    (net (code "361") (name "unconnected-(U2-PWM13-Pad20)") (class "Default")
      (node (ref "U2") (pin "20") (pinfunction "PWM13_20") (pintype "output"))
    )
    (net (code "362") (name "unconnected-(U2-PWM14-Pad21)") (class "Default")
      (node (ref "U2") (pin "21") (pinfunction "PWM14_21") (pintype "output"))
    )
    (net (code "363") (name "unconnected-(U2-PWM15-Pad22)") (class "Default")
      (node (ref "U2") (pin "22") (pinfunction "PWM15_22") (pintype "output"))
    )
    (net (code "364") (name "unconnected-(U3-ADC6-Pad19)") (class "Default")
      (node (ref "U3") (pin "19") (pinfunction "ADC6_19") (pintype "bidirectional"))
    )
    (net (code "365") (name "unconnected-(U3-ADC7-Pad22)") (class "Default")
      (node (ref "U3") (pin "22") (pinfunction "ADC7_22") (pintype "bidirectional"))
    )
    (net (code "366") (name "unconnected-(U3-AREF-Pad20)") (class "Default")
      (node (ref "U3") (pin "20") (pinfunction "AREF_20") (pintype "bidirectional"))
    )
    (net (code "367") (name "unconnected-(U3-PD0(RXD)-Pad30)") (class "Default")
      (node (ref "U3") (pin "30") (pinfunction "PD0(RXD)_30") (pintype "bidirectional"))
    )
    (net (code "368") (name "unconnected-(U3-PD1(TXD)-Pad31)") (class "Default")
      (node (ref "U3") (pin "31") (pinfunction "PD1(TXD)_31") (pintype "bidirectional"))
    )
    (net (code "369") (name "unconnected-(U5-IN2-Pad4)") (class "Default")
      (node (ref "U5") (pin "4") (pinfunction "IN2_4") (pintype "bidirectional"))
    )
    (net (code "370") (name "unconnected-(U5-VDD2-Pad16)") (class "Default")
      (node (ref "U5") (pin "16") (pinfunction "VDD2_16") (pintype "bidirectional"))
    )
    (net (code "371") (name "unconnected-(U6-OUT1-Pad14)") (class "Default")
      (node (ref "U6") (pin "14") (pinfunction "OUT1_14") (pintype "bidirectional"))
    )
    (net (code "372") (name "unconnected-(U10-N{slash}C-Pad6)") (class "Default")
      (node (ref "U10") (pin "6") (pinfunction "N/C_6") (pintype "bidirectional"))
    )
    (net (code "373") (name "unconnected-(U10-N{slash}C2-Pad7)") (class "Default")
      (node (ref "U10") (pin "7") (pinfunction "N/C2_7") (pintype "bidirectional"))
    )
    (net (code "374") (name "unconnected-(U10-N{slash}C3-Pad8)") (class "Default")
      (node (ref "U10") (pin "8") (pinfunction "N/C3_8") (pintype "bidirectional"))
    )
    (net (code "375") (name "unconnected-(U11-ADDR-Pad1)") (class "Default")
      (node (ref "U11") (pin "1") (pinfunction "ADDR_1") (pintype "bidirectional"))
    )
    (net (code "376") (name "unconnected-(U11-ALERT{slash}RDY-Pad2)") (class "Default")
      (node (ref "U11") (pin "2") (pinfunction "ALERT/RDY_2") (pintype "bidirectional"))
    )
    (net (code "377") (name "unconnected-(U13-ADDR-Pad1)") (class "Default")
      (node (ref "U13") (pin "1") (pinfunction "ADDR_1") (pintype "bidirectional"))
    )
    (net (code "378") (name "unconnected-(U13-ALERT{slash}RDY-Pad2)") (class "Default")
      (node (ref "U13") (pin "2") (pinfunction "ALERT/RDY_2") (pintype "bidirectional"))
    )
    (net (code "379") (name "unconnected-(U15-N{slash}C-Pad6)") (class "Default")
      (node (ref "U15") (pin "6") (pinfunction "N/C_6") (pintype "bidirectional"))
    )
    (net (code "380") (name "unconnected-(U15-N{slash}C2-Pad7)") (class "Default")
      (node (ref "U15") (pin "7") (pinfunction "N/C2_7") (pintype "bidirectional"))
    )
    (net (code "381") (name "unconnected-(U15-N{slash}C3-Pad8)") (class "Default")
      (node (ref "U15") (pin "8") (pinfunction "N/C3_8") (pintype "bidirectional"))
    )
    (net (code "382") (name "unconnected-(U16-A2-Pad15)") (class "Default")
      (node (ref "U16") (pin "15") (pinfunction "A2_15") (pintype "bidirectional"))
    )
    (net (code "383") (name "unconnected-(U16-A3-Pad11)") (class "Default")
      (node (ref "U16") (pin "11") (pinfunction "A3_11") (pintype "bidirectional"))
    )
    (net (code "384") (name "unconnected-(U16-B2-Pad2)") (class "Default")
      (node (ref "U16") (pin "2") (pinfunction "B2_2") (pintype "bidirectional"))
    )
    (net (code "385") (name "unconnected-(U16-B3-Pad4)") (class "Default")
      (node (ref "U16") (pin "4") (pinfunction "B3_4") (pintype "bidirectional"))
    )
    (net (code "386") (name "unconnected-(U20-~{MR}-Pad3)") (class "Default")
      (node (ref "U20") (pin "3") (pinfunction "~{MR}_3") (pintype "bidirectional"))
    )
    (net (code "387") (name "unconnected-(U47-CH-Pad11)") (class "Default")
      (node (ref "U47") (pin "11") (pinfunction "CH_11") (pintype "bidirectional"))
    )
    (net (code "388") (name "unconnected-(U49-CH-Pad11)") (class "Default")
      (node (ref "U49") (pin "11") (pinfunction "CH_11") (pintype "bidirectional"))
    )
    (net (code "389") (name "unconnected-(VREG-BP-Pad4)") (class "Default")
      (node (ref "VREG") (pin "4") (pinfunction "BP_4") (pintype "input"))
    )
    (net (code "390") (name "~{FAULT}") (class "Default")
      (node (ref "IC2") (pin "24") (pinfunction "(OC1A/PCINT5)PB5_24") (pintype "bidirectional"))
    )
    (net (code "391") (name "~{RESET}") (class "Default")
      (node (ref "C20") (pin "1") (pinfunction "1_1") (pintype "passive"))
      (node (ref "IC2") (pin "30") (pinfunction "RESET_30") (pintype "input"))
      (node (ref "ICSP") (pin "5") (pinfunction "5_5") (pintype "passive"))
      (node (ref "R26") (pin "1") (pinfunction "1_1") (pintype "passive"))
      (node (ref "S1") (pin "1") (pinfunction "1_1") (pintype "passive"))
      (node (ref "S1") (pin "2") (pinfunction "2_2") (pintype "passive"))
    )
    (net (code "392") (name "~{RST}") (class "Default")
      (node (ref "U1") (pin "1") (pinfunction "~{RESET}_1") (pintype "bidirectional"))
    )
  )
)
